# Axis_Channel.net
KiCad netlist of a schematic drawn in Altium Designer
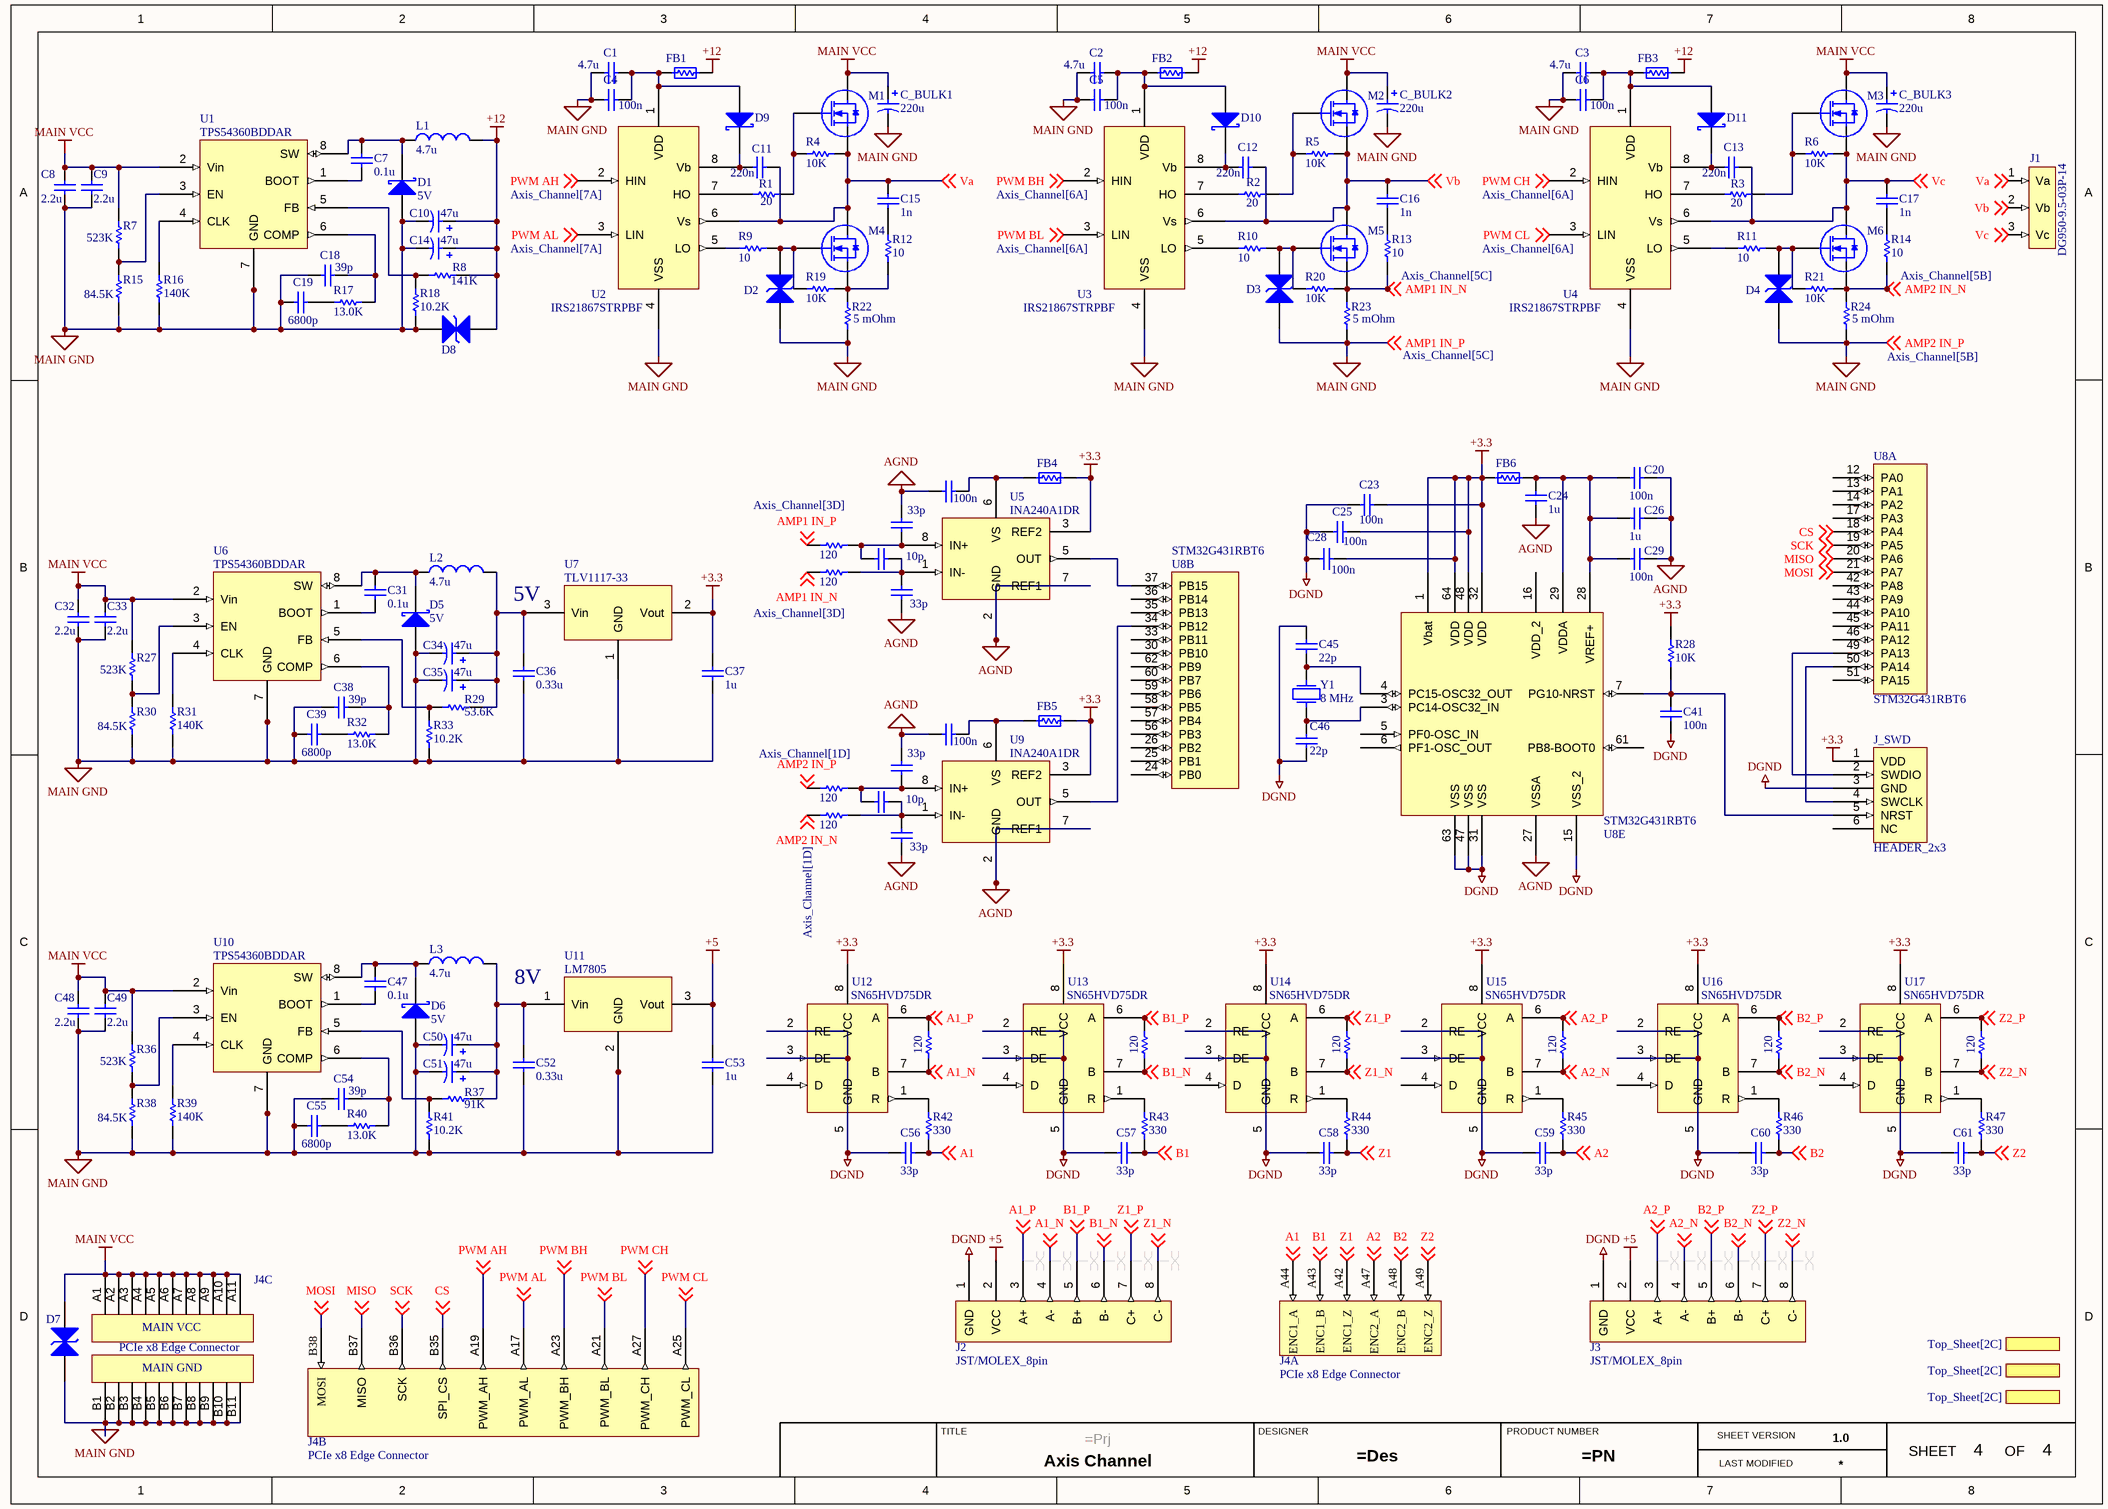
[diagram p0: Axis_Channel.SchDoc]

(export (version "E")
  (design (tool "Eeschema 10.0.6"))
  (components
    (comp (ref "C1")
      (value "4.7u")
      (footprint "1206")
      (description "2.2u-10u")
      (fields (field (name "Comment") "Capacitor 1206"))
      (libsource (lib "Power_Components") (part "Capacitor 1206"))
    )
    (comp (ref "C2")
      (value "4.7u")
      (footprint "1206")
      (description "2.2u-10u")
      (fields (field (name "Comment") "Capacitor 1206"))
      (libsource (lib "Power_Components") (part "Capacitor 1206"))
    )
    (comp (ref "C3")
      (value "4.7u")
      (footprint "1206")
      (description "2.2u-10u")
      (fields (field (name "Comment") "Capacitor 1206"))
      (libsource (lib "Power_Components") (part "Capacitor 1206"))
    )
    (comp (ref "C4")
      (value "100n")
      (footprint "0805")
      (description "0.1u-1u")
      (fields (field (name "Comment") "Capacitor 0805"))
      (libsource (lib "Power_Components") (part "Capacitor 0805"))
    )
    (comp (ref "C5")
      (value "100n")
      (footprint "0805")
      (description "0.1u-1u")
      (fields (field (name "Comment") "Capacitor 0805"))
      (libsource (lib "Power_Components") (part "Capacitor 0805"))
    )
    (comp (ref "C6")
      (value "100n")
      (footprint "0805")
      (description "0.1u-1u")
      (fields (field (name "Comment") "Capacitor 0805"))
      (libsource (lib "Power_Components") (part "Capacitor 0805"))
    )
    (comp (ref "C7")
      (value "0.1u")
      (footprint "0805")
      (description "0.1u-1u")
      (fields (field (name "Comment") "Alum SMD Cap"))
      (libsource (lib "Power_Components") (part "Capacitor 0805"))
    )
    (comp (ref "C8")
      (value "2.2u")
      (footprint "1206")
      (description "2.2u-10u")
      (fields (field (name "Comment") "Alum SMD Cap"))
      (libsource (lib "Power_Components") (part "Capacitor 1206"))
    )
    (comp (ref "C9")
      (value "2.2u")
      (footprint "1206")
      (description "2.2u-10u")
      (fields (field (name "Comment") "Capacitor 1206"))
      (libsource (lib "Power_Components") (part "Capacitor 1206"))
    )
    (comp (ref "C10")
      (value "47u")
      (footprint "ECAP D6.3xL7.7mm")
      (fields (field (name "Comment") "Alum SMD Cap"))
      (libsource (lib "Power_Components") (part "RVT1H470M0607 47UF 50V"))
    )
    (comp (ref "C11")
      (value "220n")
      (footprint "0805")
      (description "0.1u-1u")
      (fields (field (name "Comment") "Capacitor 0805"))
      (libsource (lib "Power_Components") (part "Capacitor 0805"))
    )
    (comp (ref "C12")
      (value "220n")
      (footprint "0805")
      (description "0.1u-1u")
      (fields (field (name "Comment") "Capacitor 0805"))
      (libsource (lib "Power_Components") (part "Capacitor 0805"))
    )
    (comp (ref "C13")
      (value "220n")
      (footprint "0805")
      (description "0.1u-1u")
      (fields (field (name "Comment") "Capacitor 0805"))
      (libsource (lib "Power_Components") (part "Capacitor 0805"))
    )
    (comp (ref "C14")
      (value "47u")
      (footprint "ECAP D6.3xL7.7mm")
      (fields (field (name "Comment") "Alum SMD Cap"))
      (libsource (lib "Power_Components") (part "RVT1H470M0607 47UF 50V"))
    )
    (comp (ref "C15")
      (value "1n")
      (footprint "0805")
      (description "0.1u-1u")
      (fields (field (name "Comment") "Capacitor 0805"))
      (libsource (lib "Power_Components") (part "Capacitor 0805"))
    )
    (comp (ref "C16")
      (value "1n")
      (footprint "0805")
      (description "0.1u-1u")
      (fields (field (name "Comment") "Capacitor 0805"))
      (libsource (lib "Power_Components") (part "Capacitor 0805"))
    )
    (comp (ref "C17")
      (value "1n")
      (footprint "0805")
      (description "0.1u-1u")
      (fields (field (name "Comment") "Capacitor 0805"))
      (libsource (lib "Power_Components") (part "Capacitor 0805"))
    )
    (comp (ref "C18")
      (value "39p")
      (footprint "0805")
      (description "0.1u-1u")
      (fields (field (name "Comment") "Capacitor"))
      (libsource (lib "Power_Components") (part "Capacitor 0805"))
    )
    (comp (ref "C19")
      (value "6800p")
      (footprint "0805")
      (description "0.1u-1u")
      (fields (field (name "Comment") "Capacitor 0805"))
      (libsource (lib "Power_Components") (part "Capacitor 0805"))
    )
    (comp (ref "C20")
      (value "100n")
      (footprint "0805")
      (description "0.1u-1u")
      (fields (field (name "Comment") "Capacitor 0805"))
      (libsource (lib "Power_Components") (part "Capacitor 0805"))
    )
    (comp (ref "C21")
      (value "Cap")
      (footprint "0805")
      (fields (field (name "PARAMETER 1") "100n"))
      (libsource (lib "") (part "Capacitor 0805_1"))
    )
    (comp (ref "C22")
      (value "Cap")
      (footprint "0805")
      (fields (field (name "PARAMETER 1") "33p"))
      (libsource (lib "") (part "Capacitor 0805_1"))
    )
    (comp (ref "C23")
      (value "100n")
      (footprint "0805")
      (description "0.1u-1u")
      (fields (field (name "Comment") "Capacitor 0805"))
      (libsource (lib "Power_Components") (part "Capacitor 0805"))
    )
    (comp (ref "C24")
      (value "1u")
      (footprint "0805")
      (description "0.1u-1u")
      (fields (field (name "Comment") "Capacitor 0805"))
      (libsource (lib "Power_Components") (part "Capacitor 0805"))
    )
    (comp (ref "C25")
      (value "100n")
      (footprint "0805")
      (description "0.1u-1u")
      (fields (field (name "Comment") "Capacitor 0805"))
      (libsource (lib "Power_Components") (part "Capacitor 0805"))
    )
    (comp (ref "C26")
      (value "1u")
      (footprint "0805")
      (description "0.1u-1u")
      (fields (field (name "Comment") "Capacitor 0805"))
      (libsource (lib "Power_Components") (part "Capacitor 0805"))
    )
    (comp (ref "C27")
      (value "Cap")
      (footprint "0805")
      (fields (field (name "PARAMETER 1") "10p"))
      (libsource (lib "") (part "Capacitor 0805_1"))
    )
    (comp (ref "C28")
      (value "100n")
      (footprint "0805")
      (description "0.1u-1u")
      (fields (field (name "Comment") "Capacitor 0805"))
      (libsource (lib "Power_Components") (part "Capacitor 0805"))
    )
    (comp (ref "C29")
      (value "100n")
      (footprint "0805")
      (description "0.1u-1u")
      (fields (field (name "Comment") "Capacitor 0805"))
      (libsource (lib "Power_Components") (part "Capacitor 0805"))
    )
    (comp (ref "C30")
      (value "Cap")
      (footprint "0805")
      (fields (field (name "PARAMETER 1") "33p"))
      (libsource (lib "") (part "Capacitor 0805_1"))
    )
    (comp (ref "C31")
      (value "0.1u")
      (footprint "0805")
      (description "0.1u-1u")
      (fields (field (name "Comment") "Alum SMD Cap"))
      (libsource (lib "Power_Components") (part "Capacitor 0805"))
    )
    (comp (ref "C32")
      (value "2.2u")
      (footprint "1206")
      (description "2.2u-10u")
      (fields (field (name "Comment") "Alum SMD Cap"))
      (libsource (lib "Power_Components") (part "Capacitor 1206"))
    )
    (comp (ref "C33")
      (value "2.2u")
      (footprint "1206")
      (description "2.2u-10u")
      (fields (field (name "Comment") "Capacitor 1206"))
      (libsource (lib "Power_Components") (part "Capacitor 1206"))
    )
    (comp (ref "C34")
      (value "47u")
      (footprint "ECAP D6.3xL7.7mm")
      (fields (field (name "Comment") "Alum SMD Cap"))
      (libsource (lib "Power_Components") (part "RVT1H470M0607 47UF 50V"))
    )
    (comp (ref "C35")
      (value "47u")
      (footprint "ECAP D6.3xL7.7mm")
      (fields (field (name "Comment") "Alum SMD Cap"))
      (libsource (lib "Power_Components") (part "RVT1H470M0607 47UF 50V"))
    )
    (comp (ref "C36")
      (value "0.33u")
      (footprint "0805")
      (description "0.1u-1u")
      (fields (field (name "Comment") "Capacitor 0805"))
      (libsource (lib "Power_Components") (part "Capacitor 0805"))
    )
    (comp (ref "C37")
      (value "1u")
      (footprint "0805")
      (description "0.1u-1u")
      (fields (field (name "Comment") "Capacitor 0805"))
      (libsource (lib "Power_Components") (part "Capacitor 0805"))
    )
    (comp (ref "C38")
      (value "39p")
      (footprint "0805")
      (description "0.1u-1u")
      (fields (field (name "Comment") "Alum SMD Cap"))
      (libsource (lib "Power_Components") (part "Capacitor 0805"))
    )
    (comp (ref "C39")
      (value "6800p")
      (footprint "0805")
      (description "0.1u-1u")
      (fields (field (name "Comment") "Capacitor 0805"))
      (libsource (lib "Power_Components") (part "Capacitor 0805"))
    )
    (comp (ref "C40")
      (value "Cap")
      (footprint "0805")
      (fields (field (name "PARAMETER 1") "100n"))
      (libsource (lib "") (part "Capacitor 0805_1"))
    )
    (comp (ref "C41")
      (value "100n")
      (footprint "0805")
      (description "0.1u-1u")
      (fields (field (name "Comment") "Capacitor 0805"))
      (libsource (lib "Power_Components") (part "Capacitor 0805"))
    )
    (comp (ref "C42")
      (value "33p")
      (footprint "0805")
      (fields (field (name "Comment") "Cap"))
      (libsource (lib "") (part "Capacitor 0805_1"))
    )
    (comp (ref "C43")
      (value "Cap")
      (footprint "0805")
      (fields (field (name "PARAMETER 1") "10p"))
      (libsource (lib "") (part "Capacitor 0805_1"))
    )
    (comp (ref "C44")
      (value "Cap")
      (footprint "0805")
      (fields (field (name "PARAMETER 1") "33p"))
      (libsource (lib "") (part "Capacitor 0805_1"))
    )
    (comp (ref "C45")
      (value "22p")
      (footprint "0805")
      (description "0.1u-1u")
      (fields (field (name "Comment") "Capacitor 0805"))
      (libsource (lib "Power_Components") (part "Capacitor 0805"))
    )
    (comp (ref "C46")
      (value "22p")
      (footprint "0805")
      (description "0.1u-1u")
      (fields (field (name "Comment") "Capacitor 0805"))
      (libsource (lib "Power_Components") (part "Capacitor 0805"))
    )
    (comp (ref "C47")
      (value "0.1u")
      (footprint "0805")
      (description "0.1u-1u")
      (fields (field (name "Comment") "Alum SMD Cap"))
      (libsource (lib "Power_Components") (part "Capacitor 0805"))
    )
    (comp (ref "C48")
      (value "2.2u")
      (footprint "1206")
      (description "2.2u-10u")
      (fields (field (name "Comment") "Alum SMD Cap"))
      (libsource (lib "Power_Components") (part "Capacitor 1206"))
    )
    (comp (ref "C49")
      (value "2.2u")
      (footprint "1206")
      (description "2.2u-10u")
      (fields (field (name "Comment") "Capacitor 1206"))
      (libsource (lib "Power_Components") (part "Capacitor 1206"))
    )
    (comp (ref "C50")
      (value "47u")
      (footprint "ECAP D6.3xL7.7mm")
      (fields (field (name "Comment") "Alum SMD Cap"))
      (libsource (lib "Power_Components") (part "RVT1H470M0607 47UF 50V"))
    )
    (comp (ref "C51")
      (value "47u")
      (footprint "ECAP D6.3xL7.7mm")
      (fields (field (name "Comment") "Alum SMD Cap"))
      (libsource (lib "Power_Components") (part "RVT1H470M0607 47UF 50V"))
    )
    (comp (ref "C52")
      (value "0.33u")
      (footprint "0805")
      (description "0.1u-1u")
      (fields (field (name "Comment") "Capacitor 0805"))
      (libsource (lib "Power_Components") (part "Capacitor 0805"))
    )
    (comp (ref "C53")
      (value "1u")
      (footprint "0805")
      (description "0.1u-1u")
      (fields (field (name "Comment") "Capacitor 0805"))
      (libsource (lib "Power_Components") (part "Capacitor 0805"))
    )
    (comp (ref "C54")
      (value "39p")
      (footprint "0805")
      (description "0.1u-1u")
      (fields (field (name "Comment") "Alum SMD Cap"))
      (libsource (lib "Power_Components") (part "Capacitor 0805"))
    )
    (comp (ref "C55")
      (value "6800p")
      (footprint "0805")
      (description "0.1u-1u")
      (fields (field (name "Comment") "Capacitor 0805"))
      (libsource (lib "Power_Components") (part "Capacitor 0805"))
    )
    (comp (ref "C56")
      (value "33p")
      (footprint "0805")
      (description "0.1u-1u")
      (fields (field (name "Comment") "Capacitor 0805"))
      (libsource (lib "Power_Components") (part "Capacitor 0805"))
    )
    (comp (ref "C57")
      (value "33p")
      (footprint "0805")
      (description "0.1u-1u")
      (fields (field (name "Comment") "Capacitor 0805"))
      (libsource (lib "Power_Components") (part "Capacitor 0805"))
    )
    (comp (ref "C58")
      (value "33p")
      (footprint "0805")
      (description "0.1u-1u")
      (fields (field (name "Comment") "Capacitor 0805"))
      (libsource (lib "Power_Components") (part "Capacitor 0805"))
    )
    (comp (ref "C59")
      (value "33p")
      (footprint "0805")
      (description "0.1u-1u")
      (fields (field (name "Comment") "Capacitor 0805"))
      (libsource (lib "Power_Components") (part "Capacitor 0805"))
    )
    (comp (ref "C60")
      (value "33p")
      (footprint "0805")
      (description "0.1u-1u")
      (fields (field (name "Comment") "Capacitor 0805"))
      (libsource (lib "Power_Components") (part "Capacitor 0805"))
    )
    (comp (ref "C61")
      (value "33p")
      (footprint "0805")
      (description "0.1u-1u")
      (fields (field (name "Comment") "Capacitor 0805"))
      (libsource (lib "Power_Components") (part "Capacitor 0805"))
    )
    (comp (ref "C_BULK1")
      (value "220u")
      (footprint "ECAP 12.5x16.5")
      (description "100V 12.5mm 16.5mm 220uF ±20% SMD,D12.5xL16.5mm Aluminum Electrolytic Capacitors - SMD ROHS")
      (fields (field (name "Comment") "Alum SMD Cap"))
      (libsource (lib "Power_Components") (part "220uF 100V 12.5mm 16.5mm"))
    )
    (comp (ref "C_BULK2")
      (value "220u")
      (footprint "ECAP 12.5x16.5")
      (description "100V 12.5mm 16.5mm 220uF ±20% SMD,D12.5xL16.5mm Aluminum Electrolytic Capacitors - SMD ROHS")
      (fields (field (name "Comment") "Alum SMD Cap"))
      (libsource (lib "Power_Components") (part "220uF 100V 12.5mm 16.5mm"))
    )
    (comp (ref "C_BULK3")
      (value "220u")
      (footprint "ECAP 12.5x16.5")
      (description "100V 12.5mm 16.5mm 220uF ±20% SMD,D12.5xL16.5mm Aluminum Electrolytic Capacitors - SMD ROHS")
      (fields (field (name "Comment") "Alum SMD Cap"))
      (libsource (lib "Power_Components") (part "220uF 100V 12.5mm 16.5mm"))
    )
    (comp (ref "D1")
      (value "5V")
      (footprint "SMB")
      (fields (field (name "Comment") "Schottky Diod"))
      (libsource (lib "Power_Components") (part "Schottky Diod"))
    )
    (comp (ref "D2")
      (value "Supressor Dual")
      (footprint "SMB")
      (description "Suppressor Dual")
      (libsource (lib "Power_Components") (part "Suppressor Dual"))
    )
    (comp (ref "D3")
      (value "Supressor Dual")
      (footprint "SMB")
      (description "Suppressor Dual")
      (libsource (lib "Power_Components") (part "Suppressor Dual"))
    )
    (comp (ref "D4")
      (value "Supressor Dual")
      (footprint "SMB")
      (description "Suppressor Dual")
      (libsource (lib "Power_Components") (part "Suppressor Dual"))
    )
    (comp (ref "D5")
      (value "5V")
      (footprint "SMB")
      (fields (field (name "Comment") "Schottky Diod"))
      (libsource (lib "Power_Components") (part "Schottky Diod"))
    )
    (comp (ref "D6")
      (value "5V")
      (footprint "SMB")
      (fields (field (name "Comment") "Schottky Diod"))
      (libsource (lib "Power_Components") (part "Schottky Diod"))
    )
    (comp (ref "D7")
      (value "Supressor Dual")
      (footprint "SMB")
      (description "Suppressor Dual")
      (libsource (lib "Power_Components") (part "Suppressor Dual"))
    )
    (comp (ref "D8")
      (value "Supressor Dual")
      (footprint "SMB")
      (description "Suppressor Dual")
      (libsource (lib "Power_Components") (part "Suppressor Dual"))
    )
    (comp (ref "D9")
      (value "Schottky Diod")
      (footprint "SMB")
      (libsource (lib "Power_Components") (part "Schottky Diod"))
    )
    (comp (ref "D10")
      (value "Schottky Diod")
      (footprint "SMB")
      (libsource (lib "Power_Components") (part "Schottky Diod"))
    )
    (comp (ref "D11")
      (value "Schottky Diod")
      (footprint "SMB")
      (libsource (lib "Power_Components") (part "Schottky Diod"))
    )
    (comp (ref "FB1")
      (value "Ferrite Bead")
      (footprint "0805")
      (description "600 ohm 100Mhz")
      (libsource (lib "Power_Components") (part "Ferrite Bead"))
    )
    (comp (ref "FB2")
      (value "Ferrite Bead")
      (footprint "0805")
      (description "600 ohm 100Mhz")
      (libsource (lib "Power_Components") (part "Ferrite Bead"))
    )
    (comp (ref "FB3")
      (value "Ferrite Bead")
      (footprint "0805")
      (description "600 ohm 100Mhz")
      (libsource (lib "Power_Components") (part "Ferrite Bead"))
    )
    (comp (ref "FB4")
      (value "Ferrite Bead")
      (footprint "0805")
      (description "600 ohm 100Mhz")
      (libsource (lib "Power_Components") (part "Ferrite Bead"))
    )
    (comp (ref "FB5")
      (value "Ferrite Bead")
      (footprint "0805")
      (description "600 ohm 100Mhz")
      (libsource (lib "Power_Components") (part "Ferrite Bead"))
    )
    (comp (ref "FB6")
      (value "Ferrite Bead")
      (footprint "0805")
      (description "600 ohm 100Mhz")
      (libsource (lib "Power_Components") (part "Ferrite Bead"))
    )
    (comp (ref "J1")
      (value "DG950-9.5-03P-14")
      (footprint "DG950-9.5-03P-14")
      (description "3 pin power")
      (libsource (lib "Power_Components") (part "DG950-9.5-03P-14"))
    )
    (comp (ref "J2")
      (value "JST/MOLEX_8pin")
      (footprint "B8B-EH-A-(LF)(SN)")
      (description "8 pin JST")
      (libsource (lib "Power_Components") (part "JST/MOLEX_8pin"))
    )
    (comp (ref "J3")
      (value "JST/MOLEX_8pin")
      (footprint "B8B-EH-A-(LF)(SN)")
      (description "8 pin JST")
      (libsource (lib "Power_Components") (part "JST/MOLEX_8pin"))
    )
    (comp (ref "J4")
      (value "PCIe x8 Edge Connector")
      (footprint "MALE_PCI_x8")
      (libsource (lib "") (part "CONN_EDGE_PCIe_x8_98P_2"))
    )
    (comp (ref "J_SWD")
      (value "HEADER_2x3")
      (footprint "HEADER_2x3")
      (libsource (lib "Power_Components") (part "HEADER_2x3"))
    )
    (comp (ref "L1")
      (value "4.7u")
      (footprint "MWSA0603S-4R7MT")
      (fields (field (name "Comment") "Inductor"))
      (libsource (lib "Power_Components") (part "Inductor"))
    )
    (comp (ref "L2")
      (value "4.7u")
      (footprint "MWSA0603S-4R7MT")
      (fields (field (name "Comment") "Inductor"))
      (libsource (lib "Power_Components") (part "Inductor"))
    )
    (comp (ref "L3")
      (value "4.7u")
      (footprint "MWSA0603S-4R7MT")
      (fields (field (name "Comment") "Inductor"))
      (libsource (lib "Power_Components") (part "Inductor"))
    )
    (comp (ref "M1")
      (value "NTMFS3D5N08XT1G")
      (footprint "SuperSO8")
      (libsource (lib "Power_Components") (part "BSC030N08NS5"))
    )
    (comp (ref "M2")
      (value "NTMFS3D5N08XT1G")
      (footprint "SuperSO8")
      (libsource (lib "Power_Components") (part "BSC030N08NS5"))
    )
    (comp (ref "M3")
      (value "NTMFS3D5N08XT1G")
      (footprint "SuperSO8")
      (libsource (lib "Power_Components") (part "BSC030N08NS5"))
    )
    (comp (ref "M4")
      (value "NTMFS3D5N08XT1G")
      (footprint "SuperSO8")
      (libsource (lib "Power_Components") (part "BSC030N08NS5"))
    )
    (comp (ref "M5")
      (value "NTMFS3D5N08XT1G")
      (footprint "SuperSO8")
      (libsource (lib "Power_Components") (part "BSC030N08NS5"))
    )
    (comp (ref "M6")
      (value "NTMFS3D5N08XT1G")
      (footprint "SuperSO8")
      (libsource (lib "Power_Components") (part "BSC030N08NS5"))
    )
    (comp (ref "R1")
      (value "20")
      (footprint "0805")
      (fields (field (name "Comment") "Resistor 0805"))
      (libsource (lib "Power_Components") (part "Resistor 0805"))
    )
    (comp (ref "R2")
      (value "20")
      (footprint "0805")
      (fields (field (name "Comment") "Resistor 0805"))
      (libsource (lib "Power_Components") (part "Resistor 0805"))
    )
    (comp (ref "R3")
      (value "20")
      (footprint "0805")
      (fields (field (name "Comment") "Resistor 0805"))
      (libsource (lib "Power_Components") (part "Resistor 0805"))
    )
    (comp (ref "R4")
      (value "10K")
      (footprint "0805")
      (fields (field (name "Comment") "Resistor 0805"))
      (libsource (lib "Power_Components") (part "Resistor 0805"))
    )
    (comp (ref "R5")
      (value "10K")
      (footprint "0805")
      (fields (field (name "Comment") "Resistor 0805"))
      (libsource (lib "Power_Components") (part "Resistor 0805"))
    )
    (comp (ref "R6")
      (value "10K")
      (footprint "0805")
      (fields (field (name "Comment") "Resistor 0805"))
      (libsource (lib "Power_Components") (part "Resistor 0805"))
    )
    (comp (ref "R7")
      (value "523K")
      (footprint "0805")
      (fields (field (name "Comment") "Resistor 0805"))
      (libsource (lib "Power_Components") (part "Resistor 0805"))
    )
    (comp (ref "R8")
      (value "141K")
      (footprint "0805")
      (fields (field (name "Comment") "Resistor 0805"))
      (libsource (lib "Power_Components") (part "Resistor 0805"))
    )
    (comp (ref "R9")
      (value "10")
      (footprint "0805")
      (fields (field (name "Comment") "Resistor 0805"))
      (libsource (lib "Power_Components") (part "Resistor 0805"))
    )
    (comp (ref "R10")
      (value "10")
      (footprint "0805")
      (fields (field (name "Comment") "Resistor 0805"))
      (libsource (lib "Power_Components") (part "Resistor 0805"))
    )
    (comp (ref "R11")
      (value "10")
      (footprint "0805")
      (fields (field (name "Comment") "Resistor 0805"))
      (libsource (lib "Power_Components") (part "Resistor 0805"))
    )
    (comp (ref "R12")
      (value "10")
      (footprint "0805")
      (fields (field (name "Comment") "Resistor 0805"))
      (libsource (lib "Power_Components") (part "Resistor 0805"))
    )
    (comp (ref "R13")
      (value "10")
      (footprint "0805")
      (fields (field (name "Comment") "Resistor 0805"))
      (libsource (lib "Power_Components") (part "Resistor 0805"))
    )
    (comp (ref "R14")
      (value "10")
      (footprint "0805")
      (fields (field (name "Comment") "Resistor 0805"))
      (libsource (lib "Power_Components") (part "Resistor 0805"))
    )
    (comp (ref "R15")
      (value "84.5K")
      (footprint "0805")
      (fields (field (name "Comment") "Resistor 0805"))
      (libsource (lib "Power_Components") (part "Resistor 0805"))
    )
    (comp (ref "R16")
      (value "140K")
      (footprint "0805")
      (fields (field (name "Comment") "Resistor 0805"))
      (libsource (lib "Power_Components") (part "Resistor 0805"))
    )
    (comp (ref "R17")
      (value "13.0K")
      (footprint "0805")
      (fields (field (name "Comment") "Resistor 0805"))
      (libsource (lib "Power_Components") (part "Resistor 0805"))
    )
    (comp (ref "R18")
      (value "10.2K")
      (footprint "0805")
      (fields (field (name "Comment") "Resistor 0805"))
      (libsource (lib "Power_Components") (part "Resistor 0805"))
    )
    (comp (ref "R19")
      (value "10K")
      (footprint "0805")
      (fields (field (name "Comment") "Resistor 0805"))
      (libsource (lib "Power_Components") (part "Resistor 0805"))
    )
    (comp (ref "R20")
      (value "10K")
      (footprint "0805")
      (fields (field (name "Comment") "Resistor 0805"))
      (libsource (lib "Power_Components") (part "Resistor 0805"))
    )
    (comp (ref "R21")
      (value "10K")
      (footprint "0805")
      (fields (field (name "Comment") "Resistor 0805"))
      (libsource (lib "Power_Components") (part "Resistor 0805"))
    )
    (comp (ref "R22")
      (value "5 mOhm")
      (footprint "2512")
      (description "Current Shunt")
      (libsource (lib "Power_Components") (part "Current Shunt"))
    )
    (comp (ref "R23")
      (value "5 mOhm")
      (footprint "2512")
      (description "Current Shunt")
      (libsource (lib "Power_Components") (part "Current Shunt"))
    )
    (comp (ref "R24")
      (value "5 mOhm")
      (footprint "2512")
      (description "Current Shunt")
      (libsource (lib "Power_Components") (part "Current Shunt"))
    )
    (comp (ref "R25")
      (value "120")
      (footprint "0805")
      (fields (field (name "Comment") "Resistor"))
      (libsource (lib "") (part "Resistor 0805_1"))
    )
    (comp (ref "R26")
      (value "120")
      (footprint "0805")
      (fields (field (name "Comment") "Resistor"))
      (libsource (lib "") (part "Resistor 0805_1"))
    )
    (comp (ref "R27")
      (value "523K")
      (footprint "0805")
      (fields (field (name "Comment") "Resistor 0805"))
      (libsource (lib "Power_Components") (part "Resistor 0805"))
    )
    (comp (ref "R28")
      (value "10K")
      (footprint "0805")
      (fields (field (name "Comment") "Resistor 0805"))
      (libsource (lib "Power_Components") (part "Resistor 0805"))
    )
    (comp (ref "R29")
      (value "53.6K")
      (footprint "0805")
      (fields (field (name "Comment") "Resistor 0805"))
      (libsource (lib "Power_Components") (part "Resistor 0805"))
    )
    (comp (ref "R30")
      (value "84.5K")
      (footprint "0805")
      (fields (field (name "Comment") "Resistor 0805"))
      (libsource (lib "Power_Components") (part "Resistor 0805"))
    )
    (comp (ref "R31")
      (value "140K")
      (footprint "0805")
      (fields (field (name "Comment") "Resistor 0805"))
      (libsource (lib "Power_Components") (part "Resistor 0805"))
    )
    (comp (ref "R32")
      (value "13.0K")
      (footprint "0805")
      (fields (field (name "Comment") "Resistor 0805"))
      (libsource (lib "Power_Components") (part "Resistor 0805"))
    )
    (comp (ref "R33")
      (value "10.2K")
      (footprint "0805")
      (fields (field (name "Comment") "Resistor 0805"))
      (libsource (lib "Power_Components") (part "Resistor 0805"))
    )
    (comp (ref "R34")
      (value "120")
      (footprint "0805")
      (fields (field (name "Comment") "Resistor"))
      (libsource (lib "") (part "Resistor 0805_1"))
    )
    (comp (ref "R35")
      (value "120")
      (footprint "0805")
      (fields (field (name "Comment") "Resistor"))
      (libsource (lib "") (part "Resistor 0805_1"))
    )
    (comp (ref "R36")
      (value "523K")
      (footprint "0805")
      (fields (field (name "Comment") "Resistor 0805"))
      (libsource (lib "Power_Components") (part "Resistor 0805"))
    )
    (comp (ref "R37")
      (value "91K")
      (footprint "0805")
      (fields (field (name "Comment") "Resistor 0805"))
      (libsource (lib "Power_Components") (part "Resistor 0805"))
    )
    (comp (ref "R38")
      (value "84.5K")
      (footprint "0805")
      (fields (field (name "Comment") "Resistor 0805"))
      (libsource (lib "Power_Components") (part "Resistor 0805"))
    )
    (comp (ref "R39")
      (value "140K")
      (footprint "0805")
      (fields (field (name "Comment") "Resistor 0805"))
      (libsource (lib "Power_Components") (part "Resistor 0805"))
    )
    (comp (ref "R40")
      (value "13.0K")
      (footprint "0805")
      (fields (field (name "Comment") "Resistor 0805"))
      (libsource (lib "Power_Components") (part "Resistor 0805"))
    )
    (comp (ref "R41")
      (value "10.2K")
      (footprint "0805")
      (fields (field (name "Comment") "Resistor 0805"))
      (libsource (lib "Power_Components") (part "Resistor 0805"))
    )
    (comp (ref "R42")
      (value "330")
      (footprint "0805")
      (fields (field (name "Comment") "Resistor 0805"))
      (libsource (lib "Power_Components") (part "Resistor 0805"))
    )
    (comp (ref "R43")
      (value "330")
      (footprint "0805")
      (fields (field (name "Comment") "Resistor 0805"))
      (libsource (lib "Power_Components") (part "Resistor 0805"))
    )
    (comp (ref "R44")
      (value "330")
      (footprint "0805")
      (fields (field (name "Comment") "Resistor 0805"))
      (libsource (lib "Power_Components") (part "Resistor 0805"))
    )
    (comp (ref "R45")
      (value "330")
      (footprint "0805")
      (fields (field (name "Comment") "Resistor 0805"))
      (libsource (lib "Power_Components") (part "Resistor 0805"))
    )
    (comp (ref "R46")
      (value "330")
      (footprint "0805")
      (fields (field (name "Comment") "Resistor 0805"))
      (libsource (lib "Power_Components") (part "Resistor 0805"))
    )
    (comp (ref "R47")
      (value "330")
      (footprint "0805")
      (fields (field (name "Comment") "Resistor 0805"))
      (libsource (lib "Power_Components") (part "Resistor 0805"))
    )
    (comp (ref "R48")
      (value "120")
      (footprint "0805")
      (fields (field (name "Comment") "Resistor"))
      (libsource (lib "Power_Components") (part "Resistor 0805"))
    )
    (comp (ref "R49")
      (value "120")
      (footprint "0805")
      (fields (field (name "Comment") "Resistor"))
      (libsource (lib "Power_Components") (part "Resistor 0805"))
    )
    (comp (ref "R50")
      (value "120")
      (footprint "0805")
      (fields (field (name "Comment") "Resistor"))
      (libsource (lib "Power_Components") (part "Resistor 0805"))
    )
    (comp (ref "R51")
      (value "120")
      (footprint "0805")
      (fields (field (name "Comment") "Resistor"))
      (libsource (lib "Power_Components") (part "Resistor 0805"))
    )
    (comp (ref "R52")
      (value "120")
      (footprint "0805")
      (fields (field (name "Comment") "Resistor"))
      (libsource (lib "Power_Components") (part "Resistor 0805"))
    )
    (comp (ref "R53")
      (value "120")
      (footprint "0805")
      (fields (field (name "Comment") "Resistor"))
      (libsource (lib "Power_Components") (part "Resistor 0805"))
    )
    (comp (ref "U1")
      (value "TPS54360BDDAR")
      (footprint "HSOIC-8-DDA")
      (description "Step down DC/DC")
      (libsource (lib "Power_Components") (part "TPS54360BDDAR"))
    )
    (comp (ref "U2")
      (value "IRS21867STRPBF")
      (footprint "SOIC-8")
      (libsource (lib "Power_Components") (part "IRS21867STRPBF"))
    )
    (comp (ref "U3")
      (value "IRS21867STRPBF")
      (footprint "SOIC-8")
      (libsource (lib "Power_Components") (part "IRS21867STRPBF"))
    )
    (comp (ref "U4")
      (value "IRS21867STRPBF")
      (footprint "SOIC-8")
      (libsource (lib "Power_Components") (part "IRS21867STRPBF"))
    )
    (comp (ref "U5")
      (value "INA240A1DR")
      (footprint "SOIC-8")
      (description "Amplifier. A1=20 V/V and +-6.75 Mohm for shunt")
      (libsource (lib "Power_Components") (part "INA240A1DR"))
    )
    (comp (ref "U6")
      (value "TPS54360BDDAR")
      (footprint "HSOIC-8-DDA")
      (description "Step down DC/DC")
      (libsource (lib "Power_Components") (part "TPS54360BDDAR"))
    )
    (comp (ref "U7")
      (value "TLV1117-33")
      (footprint "SOT-223")
      (description "LDO 3.3V")
      (libsource (lib "Power_Components") (part "TLV1117-33IDCYR"))
    )
    (comp (ref "U8")
      (value "STM32G431RBT6")
      (footprint "LQFP-64_10x10_P0.5")
      (description "STM32 with ADC")
      (libsource (lib "Power_Components") (part "STM32G431RBT6"))
    )
    (comp (ref "U9")
      (value "INA240A1DR")
      (footprint "SOIC-8")
      (description "Amplifier. A1=20 V/V and +-6.75 Mohm for shunt")
      (libsource (lib "Power_Components") (part "INA240A1DR"))
    )
    (comp (ref "U10")
      (value "TPS54360BDDAR")
      (footprint "HSOIC-8-DDA")
      (description "Step down DC/DC")
      (libsource (lib "Power_Components") (part "TPS54360BDDAR"))
    )
    (comp (ref "U11")
      (value "LM7805")
      (footprint "TO-263-3")
      (description "Output Current up to 1A")
      (libsource (lib "Power_Components") (part "LM7805"))
    )
    (comp (ref "U12")
      (value "SN65HVD75DR")
      (footprint "SOIC-8")
      (description "20 Mbps RS-422/485")
      (libsource (lib "Power_Components") (part "SN65HVD75DR"))
    )
    (comp (ref "U13")
      (value "SN65HVD75DR")
      (footprint "SOIC-8")
      (description "20 Mbps RS-422/485")
      (libsource (lib "Power_Components") (part "SN65HVD75DR"))
    )
    (comp (ref "U14")
      (value "SN65HVD75DR")
      (footprint "SOIC-8")
      (description "20 Mbps RS-422/485")
      (libsource (lib "Power_Components") (part "SN65HVD75DR"))
    )
    (comp (ref "U15")
      (value "SN65HVD75DR")
      (footprint "SOIC-8")
      (description "20 Mbps RS-422/485")
      (libsource (lib "Power_Components") (part "SN65HVD75DR"))
    )
    (comp (ref "U16")
      (value "SN65HVD75DR")
      (footprint "SOIC-8")
      (description "20 Mbps RS-422/485")
      (libsource (lib "Power_Components") (part "SN65HVD75DR"))
    )
    (comp (ref "U17")
      (value "SN65HVD75DR")
      (footprint "SOIC-8")
      (description "20 Mbps RS-422/485")
      (libsource (lib "Power_Components") (part "SN65HVD75DR"))
    )
    (comp (ref "Y1")
      (value "8 MHz")
      (footprint "hc-49sm")
      (fields (field (name "Comment") "OSC"))
      (libsource (lib "Power_Components") (part "Crystal"))
    )
  )
  (nets
    (net (code "2") (name "+3.3") (class "Default")
      (node (ref "C23") (pin "2") (pinfunction "2_2") (pintype "passive"))
      (node (ref "C25") (pin "2") (pinfunction "2_2") (pintype "passive"))
      (node (ref "C28") (pin "2") (pinfunction "2_2") (pintype "passive"))
      (node (ref "C37") (pin "2") (pinfunction "2_2") (pintype "passive"))
      (node (ref "FB4") (pin "2") (pinfunction "2_2") (pintype "passive"))
      (node (ref "FB5") (pin "2") (pinfunction "2_2") (pintype "passive"))
      (node (ref "FB6") (pin "1") (pinfunction "1_1") (pintype "passive"))
      (node (ref "J_SWD") (pin "1") (pinfunction "VDD_1") (pintype "passive"))
      (node (ref "R28") (pin "2") (pinfunction "2_2") (pintype "passive"))
      (node (ref "U12") (pin "8") (pinfunction "VCC_8") (pintype "passive"))
      (node (ref "U13") (pin "8") (pinfunction "VCC_8") (pintype "passive"))
      (node (ref "U14") (pin "8") (pinfunction "VCC_8") (pintype "passive"))
      (node (ref "U15") (pin "8") (pinfunction "VCC_8") (pintype "passive"))
      (node (ref "U16") (pin "8") (pinfunction "VCC_8") (pintype "passive"))
      (node (ref "U17") (pin "8") (pinfunction "VCC_8") (pintype "passive"))
      (node (ref "U5") (pin "3") (pinfunction "REF2_3") (pintype "passive"))
      (node (ref "U7") (pin "2") (pinfunction "Vout_2") (pintype "passive"))
      (node (ref "U7") (pin "4") (pinfunction "Vout_4") (pintype "passive"))
      (node (ref "U8") (pin "1") (pinfunction "Vbat_1") (pintype "passive"))
      (node (ref "U8") (pin "32") (pinfunction "VDD_32") (pintype "passive"))
      (node (ref "U8") (pin "48") (pinfunction "VDD_48") (pintype "passive"))
      (node (ref "U8") (pin "64") (pinfunction "VDD_64") (pintype "passive"))
      (node (ref "U9") (pin "3") (pinfunction "REF2_3") (pintype "passive"))
    )
    (net (code "3") (name "+5") (class "Default")
      (node (ref "C53") (pin "2") (pinfunction "2_2") (pintype "passive"))
      (node (ref "J2") (pin "2") (pinfunction "VCC_2") (pintype "passive"))
      (node (ref "J3") (pin "2") (pinfunction "VCC_2") (pintype "passive"))
      (node (ref "U11") (pin "3") (pinfunction "Vout_3") (pintype "passive"))
    )
    (net (code "4") (name "+12") (class "Default")
      (node (ref "C10") (pin "1") (pinfunction "1_1") (pintype "passive"))
      (node (ref "C14") (pin "1") (pinfunction "1_1") (pintype "passive"))
      (node (ref "D8") (pin "2") (pinfunction "2_2") (pintype "passive"))
      (node (ref "FB1") (pin "2") (pinfunction "2_2") (pintype "passive"))
      (node (ref "FB2") (pin "2") (pinfunction "2_2") (pintype "passive"))
      (node (ref "FB3") (pin "2") (pinfunction "2_2") (pintype "passive"))
      (node (ref "L1") (pin "2") (pinfunction "2_2") (pintype "passive"))
      (node (ref "R8") (pin "1") (pinfunction "1_1") (pintype "passive"))
    )
    (net (code "7") (name "A1") (class "Default")
      (node (ref "C56") (pin "2") (pinfunction "2_2") (pintype "passive"))
      (node (ref "J4") (pin "A44") (pinfunction "ENC1_A_A44") (pintype "input"))
      (node (ref "R42") (pin "2") (pinfunction "2_2") (pintype "passive"))
    )
    (net (code "8") (name "A1_N") (class "Default")
      (node (ref "J2") (pin "4") (pinfunction "A-_4") (pintype "output"))
      (node (ref "R48") (pin "2") (pinfunction "2_2") (pintype "passive"))
      (node (ref "U12") (pin "7") (pinfunction "B_7") (pintype "passive"))
    )
    (net (code "9") (name "A1_P") (class "Default")
      (node (ref "J2") (pin "3") (pinfunction "A+_3") (pintype "output"))
      (node (ref "R48") (pin "1") (pinfunction "1_1") (pintype "passive"))
      (node (ref "U12") (pin "6") (pinfunction "A_6") (pintype "passive"))
    )
    (net (code "10") (name "A2") (class "Default")
      (node (ref "C59") (pin "2") (pinfunction "2_2") (pintype "passive"))
      (node (ref "J4") (pin "A47") (pinfunction "ENC2_A_A47") (pintype "input"))
      (node (ref "R45") (pin "2") (pinfunction "2_2") (pintype "passive"))
    )
    (net (code "11") (name "A2_N") (class "Default")
      (node (ref "J3") (pin "4") (pinfunction "A-_4") (pintype "output"))
      (node (ref "R51") (pin "2") (pinfunction "2_2") (pintype "passive"))
      (node (ref "U15") (pin "7") (pinfunction "B_7") (pintype "passive"))
    )
    (net (code "12") (name "A2_P") (class "Default")
      (node (ref "J3") (pin "3") (pinfunction "A+_3") (pintype "output"))
      (node (ref "R51") (pin "1") (pinfunction "1_1") (pintype "passive"))
      (node (ref "U15") (pin "6") (pinfunction "A_6") (pintype "passive"))
    )
    (net (code "13") (name "AGND") (class "Default")
      (node (ref "C20") (pin "2") (pinfunction "2_2") (pintype "passive"))
      (node (ref "C21") (pin "2") (pinfunction "2_2") (pintype "passive"))
      (node (ref "C22") (pin "2") (pinfunction "2_2") (pintype "passive"))
      (node (ref "C24") (pin "1") (pinfunction "1_1") (pintype "passive"))
      (node (ref "C26") (pin "2") (pinfunction "2_2") (pintype "passive"))
      (node (ref "C29") (pin "2") (pinfunction "2_2") (pintype "passive"))
      (node (ref "C30") (pin "1") (pinfunction "1_1") (pintype "passive"))
      (node (ref "C40") (pin "2") (pinfunction "2_2") (pintype "passive"))
      (node (ref "C42") (pin "2") (pinfunction "2_2") (pintype "passive"))
      (node (ref "C44") (pin "1") (pinfunction "1_1") (pintype "passive"))
      (node (ref "U5") (pin "2") (pinfunction "GND_2") (pintype "passive"))
      (node (ref "U5") (pin "7") (pinfunction "REF1_7") (pintype "passive"))
      (node (ref "U8") (pin "27") (pinfunction "VSSA_27") (pintype "passive"))
      (node (ref "U9") (pin "2") (pinfunction "GND_2") (pintype "passive"))
      (node (ref "U9") (pin "7") (pinfunction "REF1_7") (pintype "passive"))
    )
    (net (code "14") (name "AMP1 IN_N") (class "Default")
      (node (ref "M5") (pin "1") (pinfunction "S_1") (pintype "passive"))
      (node (ref "M5") (pin "2") (pinfunction "S_2") (pintype "passive"))
      (node (ref "M5") (pin "3") (pinfunction "S_3") (pintype "passive"))
      (node (ref "R13") (pin "1") (pinfunction "1_1") (pintype "passive"))
      (node (ref "R20") (pin "1") (pinfunction "1_1") (pintype "passive"))
      (node (ref "R23") (pin "2") (pinfunction "2_2") (pintype "passive"))
      (node (ref "R26") (pin "1") (pinfunction "1_1") (pintype "passive"))
    )
    (net (code "15") (name "AMP1 IN_P") (class "Default")
      (node (ref "C1") (pin "2") (pinfunction "2_2") (pintype "passive"))
      (node (ref "C10") (pin "2") (pinfunction "2_2") (pintype "passive"))
      (node (ref "C14") (pin "2") (pinfunction "2_2") (pintype "passive"))
      (node (ref "C18") (pin "2") (pinfunction "2_2") (pintype "passive"))
      (node (ref "C19") (pin "2") (pinfunction "2_2") (pintype "passive"))
      (node (ref "C2") (pin "2") (pinfunction "2_2") (pintype "passive"))
      (node (ref "C3") (pin "2") (pinfunction "2_2") (pintype "passive"))
      (node (ref "C32") (pin "1") (pinfunction "1_1") (pintype "passive"))
      (node (ref "C33") (pin "1") (pinfunction "1_1") (pintype "passive"))
      (node (ref "C34") (pin "2") (pinfunction "2_2") (pintype "passive"))
      (node (ref "C35") (pin "2") (pinfunction "2_2") (pintype "passive"))
      (node (ref "C36") (pin "1") (pinfunction "1_1") (pintype "passive"))
      (node (ref "C37") (pin "1") (pinfunction "1_1") (pintype "passive"))
      (node (ref "C38") (pin "2") (pinfunction "2_2") (pintype "passive"))
      (node (ref "C39") (pin "2") (pinfunction "2_2") (pintype "passive"))
      (node (ref "C4") (pin "2") (pinfunction "2_2") (pintype "passive"))
      (node (ref "C48") (pin "1") (pinfunction "1_1") (pintype "passive"))
      (node (ref "C49") (pin "1") (pinfunction "1_1") (pintype "passive"))
      (node (ref "C5") (pin "2") (pinfunction "2_2") (pintype "passive"))
      (node (ref "C50") (pin "2") (pinfunction "2_2") (pintype "passive"))
      (node (ref "C51") (pin "2") (pinfunction "2_2") (pintype "passive"))
      (node (ref "C52") (pin "1") (pinfunction "1_1") (pintype "passive"))
      (node (ref "C53") (pin "1") (pinfunction "1_1") (pintype "passive"))
      (node (ref "C54") (pin "2") (pinfunction "2_2") (pintype "passive"))
      (node (ref "C55") (pin "2") (pinfunction "2_2") (pintype "passive"))
      (node (ref "C6") (pin "2") (pinfunction "2_2") (pintype "passive"))
      (node (ref "C8") (pin "1") (pinfunction "1_1") (pintype "passive"))
      (node (ref "C9") (pin "1") (pinfunction "1_1") (pintype "passive"))
      (node (ref "C_BULK1") (pin "2") (pinfunction "2_2") (pintype "passive"))
      (node (ref "C_BULK2") (pin "2") (pinfunction "2_2") (pintype "passive"))
      (node (ref "C_BULK3") (pin "2") (pinfunction "2_2") (pintype "passive"))
      (node (ref "D1") (pin "1") (pinfunction "A_1") (pintype "passive"))
      (node (ref "D2") (pin "1") (pinfunction "1_1") (pintype "passive"))
      (node (ref "D3") (pin "1") (pinfunction "1_1") (pintype "passive"))
      (node (ref "D4") (pin "1") (pinfunction "1_1") (pintype "passive"))
      (node (ref "D5") (pin "1") (pinfunction "A_1") (pintype "passive"))
      (node (ref "D6") (pin "1") (pinfunction "A_1") (pintype "passive"))
      (node (ref "D7") (pin "1") (pinfunction "1_1") (pintype "passive"))
      (node (ref "D8") (pin "1") (pinfunction "1_1") (pintype "passive"))
      (node (ref "J4") (pin "B1") (pinfunction "A19_B1") (pintype "power_in"))
      (node (ref "J4") (pin "B10") (pinfunction "A28_B10") (pintype "power_in"))
      (node (ref "J4") (pin "B11") (pinfunction "A29_B11") (pintype "power_in"))
      (node (ref "J4") (pin "B2") (pinfunction "A20_B2") (pintype "power_in"))
      (node (ref "J4") (pin "B3") (pinfunction "A21_B3") (pintype "power_in"))
      (node (ref "J4") (pin "B4") (pinfunction "A22_B4") (pintype "power_in"))
      (node (ref "J4") (pin "B5") (pinfunction "A23_B5") (pintype "power_in"))
      (node (ref "J4") (pin "B6") (pinfunction "A24_B6") (pintype "power_in"))
      (node (ref "J4") (pin "B7") (pinfunction "A25_B7") (pintype "power_in"))
      (node (ref "J4") (pin "B8") (pinfunction "A26_B8") (pintype "power_in"))
      (node (ref "J4") (pin "B9") (pinfunction "A27_B9") (pintype "power_in"))
      (node (ref "R15") (pin "1") (pinfunction "1_1") (pintype "passive"))
      (node (ref "R16") (pin "1") (pinfunction "1_1") (pintype "passive"))
      (node (ref "R18") (pin "1") (pinfunction "1_1") (pintype "passive"))
      (node (ref "R22") (pin "1") (pinfunction "1_1") (pintype "passive"))
      (node (ref "R23") (pin "1") (pinfunction "1_1") (pintype "passive"))
      (node (ref "R24") (pin "1") (pinfunction "1_1") (pintype "passive"))
      (node (ref "R25") (pin "1") (pinfunction "1_1") (pintype "passive"))
      (node (ref "R30") (pin "1") (pinfunction "1_1") (pintype "passive"))
      (node (ref "R31") (pin "1") (pinfunction "1_1") (pintype "passive"))
      (node (ref "R33") (pin "1") (pinfunction "1_1") (pintype "passive"))
      (node (ref "R34") (pin "1") (pinfunction "1_1") (pintype "passive"))
      (node (ref "R38") (pin "1") (pinfunction "1_1") (pintype "passive"))
      (node (ref "R39") (pin "1") (pinfunction "1_1") (pintype "passive"))
      (node (ref "R41") (pin "1") (pinfunction "1_1") (pintype "passive"))
      (node (ref "U1") (pin "7") (pinfunction "GND_7") (pintype "passive"))
      (node (ref "U1") (pin "9") (pinfunction "GND_9") (pintype "passive"))
      (node (ref "U10") (pin "7") (pinfunction "GND_7") (pintype "passive"))
      (node (ref "U10") (pin "9") (pinfunction "GND_9") (pintype "passive"))
      (node (ref "U11") (pin "2") (pinfunction "GND_2") (pintype "passive"))
      (node (ref "U11") (pin "4") (pinfunction "GND_4") (pintype "passive"))
      (node (ref "U2") (pin "4") (pinfunction "VSS_4") (pintype "passive"))
      (node (ref "U3") (pin "4") (pinfunction "VSS_4") (pintype "passive"))
      (node (ref "U4") (pin "4") (pinfunction "VSS_4") (pintype "passive"))
      (node (ref "U6") (pin "7") (pinfunction "GND_7") (pintype "passive"))
      (node (ref "U6") (pin "9") (pinfunction "GND_9") (pintype "passive"))
      (node (ref "U7") (pin "1") (pinfunction "GND_1") (pintype "passive"))
    )
    (net (code "16") (name "AMP2 IN_N") (class "Default")
      (node (ref "M6") (pin "1") (pinfunction "S_1") (pintype "passive"))
      (node (ref "M6") (pin "2") (pinfunction "S_2") (pintype "passive"))
      (node (ref "M6") (pin "3") (pinfunction "S_3") (pintype "passive"))
      (node (ref "R14") (pin "1") (pinfunction "1_1") (pintype "passive"))
      (node (ref "R21") (pin "1") (pinfunction "1_1") (pintype "passive"))
      (node (ref "R24") (pin "2") (pinfunction "2_2") (pintype "passive"))
      (node (ref "R35") (pin "1") (pinfunction "1_1") (pintype "passive"))
    )
    (net (code "17") (name "B1") (class "Default")
      (node (ref "C57") (pin "2") (pinfunction "2_2") (pintype "passive"))
      (node (ref "J4") (pin "A43") (pinfunction "ENC1_B_A43") (pintype "input"))
      (node (ref "R43") (pin "2") (pinfunction "2_2") (pintype "passive"))
    )
    (net (code "18") (name "B1_N") (class "Default")
      (node (ref "J2") (pin "6") (pinfunction "B-_6") (pintype "output"))
      (node (ref "R49") (pin "2") (pinfunction "2_2") (pintype "passive"))
      (node (ref "U13") (pin "7") (pinfunction "B_7") (pintype "passive"))
    )
    (net (code "19") (name "B1_P") (class "Default")
      (node (ref "J2") (pin "5") (pinfunction "B+_5") (pintype "output"))
      (node (ref "R49") (pin "1") (pinfunction "1_1") (pintype "passive"))
      (node (ref "U13") (pin "6") (pinfunction "A_6") (pintype "passive"))
    )
    (net (code "20") (name "B2") (class "Default")
      (node (ref "C60") (pin "2") (pinfunction "2_2") (pintype "passive"))
      (node (ref "J4") (pin "A48") (pinfunction "ENC2_B_A48") (pintype "input"))
      (node (ref "R46") (pin "2") (pinfunction "2_2") (pintype "passive"))
    )
    (net (code "21") (name "B2_N") (class "Default")
      (node (ref "J3") (pin "6") (pinfunction "B-_6") (pintype "output"))
      (node (ref "R52") (pin "2") (pinfunction "2_2") (pintype "passive"))
      (node (ref "U16") (pin "7") (pinfunction "B_7") (pintype "passive"))
    )
    (net (code "22") (name "B2_P") (class "Default")
      (node (ref "J3") (pin "5") (pinfunction "B+_5") (pintype "output"))
      (node (ref "R52") (pin "1") (pinfunction "1_1") (pintype "passive"))
      (node (ref "U16") (pin "6") (pinfunction "A_6") (pintype "passive"))
    )
    (net (code "23") (name "CS") (class "Default")
      (node (ref "J4") (pin "B35") (pinfunction "SPI_CS_B35") (pintype "output"))
      (node (ref "U8") (pin "18") (pinfunction "PA4_18") (pintype "bidirectional"))
    )
    (net (code "24") (name "DGND") (class "Default")
      (node (ref "C23") (pin "1") (pinfunction "1_1") (pintype "passive"))
      (node (ref "C25") (pin "1") (pinfunction "1_1") (pintype "passive"))
      (node (ref "C28") (pin "1") (pinfunction "1_1") (pintype "passive"))
      (node (ref "C41") (pin "1") (pinfunction "1_1") (pintype "passive"))
      (node (ref "C45") (pin "1") (pinfunction "1_1") (pintype "passive"))
      (node (ref "C46") (pin "1") (pinfunction "1_1") (pintype "passive"))
      (node (ref "C56") (pin "1") (pinfunction "1_1") (pintype "passive"))
      (node (ref "C57") (pin "1") (pinfunction "1_1") (pintype "passive"))
      (node (ref "C58") (pin "1") (pinfunction "1_1") (pintype "passive"))
      (node (ref "C59") (pin "1") (pinfunction "1_1") (pintype "passive"))
      (node (ref "C60") (pin "1") (pinfunction "1_1") (pintype "passive"))
      (node (ref "C61") (pin "1") (pinfunction "1_1") (pintype "passive"))
      (node (ref "J2") (pin "1") (pinfunction "GND_1") (pintype "passive"))
      (node (ref "J3") (pin "1") (pinfunction "GND_1") (pintype "passive"))
      (node (ref "J_SWD") (pin "3") (pinfunction "GND_3") (pintype "passive"))
      (node (ref "U12") (pin "2") (pinfunction "RE_2") (pintype "passive"))
      (node (ref "U12") (pin "3") (pinfunction "DE_3") (pintype "input"))
      (node (ref "U12") (pin "5") (pinfunction "GND_5") (pintype "passive"))
      (node (ref "U13") (pin "2") (pinfunction "RE_2") (pintype "passive"))
      (node (ref "U13") (pin "3") (pinfunction "DE_3") (pintype "input"))
      (node (ref "U13") (pin "5") (pinfunction "GND_5") (pintype "passive"))
      (node (ref "U14") (pin "2") (pinfunction "RE_2") (pintype "passive"))
      (node (ref "U14") (pin "3") (pinfunction "DE_3") (pintype "input"))
      (node (ref "U14") (pin "5") (pinfunction "GND_5") (pintype "passive"))
      (node (ref "U15") (pin "2") (pinfunction "RE_2") (pintype "passive"))
      (node (ref "U15") (pin "3") (pinfunction "DE_3") (pintype "input"))
      (node (ref "U15") (pin "5") (pinfunction "GND_5") (pintype "passive"))
      (node (ref "U16") (pin "2") (pinfunction "RE_2") (pintype "passive"))
      (node (ref "U16") (pin "3") (pinfunction "DE_3") (pintype "input"))
      (node (ref "U16") (pin "5") (pinfunction "GND_5") (pintype "passive"))
      (node (ref "U17") (pin "2") (pinfunction "RE_2") (pintype "passive"))
      (node (ref "U17") (pin "3") (pinfunction "DE_3") (pintype "input"))
      (node (ref "U17") (pin "5") (pinfunction "GND_5") (pintype "passive"))
      (node (ref "U8") (pin "15") (pinfunction "VSS_2_15") (pintype "passive"))
      (node (ref "U8") (pin "31") (pinfunction "VSS_31") (pintype "passive"))
      (node (ref "U8") (pin "47") (pinfunction "VSS_47") (pintype "passive"))
      (node (ref "U8") (pin "63") (pinfunction "VSS_63") (pintype "passive"))
    )
    (net (code "25") (name "MAIN VCC") (class "Default")
      (node (ref "C32") (pin "2") (pinfunction "2_2") (pintype "passive"))
      (node (ref "C33") (pin "2") (pinfunction "2_2") (pintype "passive"))
      (node (ref "C48") (pin "2") (pinfunction "2_2") (pintype "passive"))
      (node (ref "C49") (pin "2") (pinfunction "2_2") (pintype "passive"))
      (node (ref "C8") (pin "2") (pinfunction "2_2") (pintype "passive"))
      (node (ref "C9") (pin "2") (pinfunction "2_2") (pintype "passive"))
      (node (ref "C_BULK1") (pin "1") (pinfunction "1_1") (pintype "passive"))
      (node (ref "C_BULK2") (pin "1") (pinfunction "1_1") (pintype "passive"))
      (node (ref "C_BULK3") (pin "1") (pinfunction "1_1") (pintype "passive"))
      (node (ref "D7") (pin "2") (pinfunction "2_2") (pintype "passive"))
      (node (ref "J4") (pin "A1") (pintype "power_in"))
      (node (ref "J4") (pin "A10") (pintype "power_in"))
      (node (ref "J4") (pin "A11") (pintype "power_in"))
      (node (ref "J4") (pin "A2") (pintype "power_in"))
      (node (ref "J4") (pin "A3") (pintype "power_in"))
      (node (ref "J4") (pin "A4") (pintype "power_in"))
      (node (ref "J4") (pin "A5") (pintype "power_in"))
      (node (ref "J4") (pin "A6") (pintype "power_in"))
      (node (ref "J4") (pin "A7") (pintype "power_in"))
      (node (ref "J4") (pin "A8") (pintype "power_in"))
      (node (ref "J4") (pin "A9") (pintype "power_in"))
      (node (ref "M1") (pin "5") (pinfunction "D_5") (pintype "passive"))
      (node (ref "M1") (pin "6") (pinfunction "D_6") (pintype "passive"))
      (node (ref "M1") (pin "7") (pinfunction "D_7") (pintype "passive"))
      (node (ref "M1") (pin "8") (pinfunction "D_8") (pintype "passive"))
      (node (ref "M2") (pin "5") (pinfunction "D_5") (pintype "passive"))
      (node (ref "M2") (pin "6") (pinfunction "D_6") (pintype "passive"))
      (node (ref "M2") (pin "7") (pinfunction "D_7") (pintype "passive"))
      (node (ref "M2") (pin "8") (pinfunction "D_8") (pintype "passive"))
      (node (ref "M3") (pin "5") (pinfunction "D_5") (pintype "passive"))
      (node (ref "M3") (pin "6") (pinfunction "D_6") (pintype "passive"))
      (node (ref "M3") (pin "7") (pinfunction "D_7") (pintype "passive"))
      (node (ref "M3") (pin "8") (pinfunction "D_8") (pintype "passive"))
      (node (ref "R27") (pin "2") (pinfunction "2_2") (pintype "passive"))
      (node (ref "R36") (pin "2") (pinfunction "2_2") (pintype "passive"))
      (node (ref "R7") (pin "2") (pinfunction "2_2") (pintype "passive"))
      (node (ref "U1") (pin "2") (pinfunction "Vin_2") (pintype "input"))
      (node (ref "U10") (pin "2") (pinfunction "Vin_2") (pintype "input"))
      (node (ref "U6") (pin "2") (pinfunction "Vin_2") (pintype "input"))
    )
    (net (code "26") (name "MISO") (class "Default")
      (node (ref "J4") (pin "B37") (pinfunction "MISO_B37") (pintype "output"))
      (node (ref "U8") (pin "20") (pinfunction "PA6_20") (pintype "bidirectional"))
    )
    (net (code "27") (name "MOSI") (class "Default")
      (node (ref "J4") (pin "B38") (pinfunction "MOSI_B38") (pintype "input"))
      (node (ref "U8") (pin "21") (pinfunction "PA7_21") (pintype "bidirectional"))
    )
    (net (code "28") (name "Net-(C15-Pad2)") (class "Default")
      (node (ref "C15") (pin "2") (pinfunction "2_2") (pintype "passive"))
      (node (ref "R12") (pin "2") (pinfunction "2_2") (pintype "passive"))
    )
    (net (code "29") (name "Net-(C16-Pad2)") (class "Default")
      (node (ref "C16") (pin "2") (pinfunction "2_2") (pintype "passive"))
      (node (ref "R13") (pin "2") (pinfunction "2_2") (pintype "passive"))
    )
    (net (code "30") (name "Net-(C17-Pad2)") (class "Default")
      (node (ref "C17") (pin "2") (pinfunction "2_2") (pintype "passive"))
      (node (ref "R14") (pin "2") (pinfunction "2_2") (pintype "passive"))
    )
    (net (code "31") (name "Net-(C19-Pad1)") (class "Default")
      (node (ref "C19") (pin "1") (pinfunction "1_1") (pintype "passive"))
      (node (ref "R17") (pin "2") (pinfunction "2_2") (pintype "passive"))
    )
    (net (code "32") (name "Net-(C39-Pad1)") (class "Default")
      (node (ref "C39") (pin "1") (pinfunction "1_1") (pintype "passive"))
      (node (ref "R32") (pin "2") (pinfunction "2_2") (pintype "passive"))
    )
    (net (code "33") (name "Net-(C55-Pad1)") (class "Default")
      (node (ref "C55") (pin "1") (pinfunction "1_1") (pintype "passive"))
      (node (ref "R40") (pin "2") (pinfunction "2_2") (pintype "passive"))
    )
    (net (code "34") (name "Net-(D1-K)") (class "Default")
      (node (ref "C7") (pin "1") (pinfunction "1_1") (pintype "passive"))
      (node (ref "D1") (pin "2") (pinfunction "K_2") (pintype "passive"))
      (node (ref "L1") (pin "1") (pinfunction "1_1") (pintype "passive"))
      (node (ref "U1") (pin "8") (pinfunction "SW_8") (pintype "bidirectional"))
    )
    (net (code "35") (name "Net-(D5-K)") (class "Default")
      (node (ref "C31") (pin "1") (pinfunction "1_1") (pintype "passive"))
      (node (ref "D5") (pin "2") (pinfunction "K_2") (pintype "passive"))
      (node (ref "L2") (pin "1") (pinfunction "1_1") (pintype "passive"))
      (node (ref "U6") (pin "8") (pinfunction "SW_8") (pintype "bidirectional"))
    )
    (net (code "36") (name "Net-(D6-K)") (class "Default")
      (node (ref "C47") (pin "1") (pinfunction "1_1") (pintype "passive"))
      (node (ref "D6") (pin "2") (pinfunction "K_2") (pintype "passive"))
      (node (ref "L3") (pin "1") (pinfunction "1_1") (pintype "passive"))
      (node (ref "U10") (pin "8") (pinfunction "SW_8") (pintype "bidirectional"))
    )
    (net (code "37") (name "Net-(D9-A)") (class "Default")
      (node (ref "C1") (pin "1") (pinfunction "1_1") (pintype "passive"))
      (node (ref "C4") (pin "1") (pinfunction "1_1") (pintype "passive"))
      (node (ref "D9") (pin "1") (pinfunction "A_1") (pintype "passive"))
      (node (ref "FB1") (pin "1") (pinfunction "1_1") (pintype "passive"))
      (node (ref "U2") (pin "1") (pinfunction "VDD_1") (pintype "power_in"))
    )
    (net (code "38") (name "Net-(D9-K)") (class "Default")
      (node (ref "C11") (pin "2") (pinfunction "2_2") (pintype "passive"))
      (node (ref "D9") (pin "2") (pinfunction "K_2") (pintype "passive"))
      (node (ref "U2") (pin "8") (pinfunction "Vb_8") (pintype "passive"))
    )
    (net (code "39") (name "Net-(D10-A)") (class "Default")
      (node (ref "C2") (pin "1") (pinfunction "1_1") (pintype "passive"))
      (node (ref "C5") (pin "1") (pinfunction "1_1") (pintype "passive"))
      (node (ref "D10") (pin "1") (pinfunction "A_1") (pintype "passive"))
      (node (ref "FB2") (pin "1") (pinfunction "1_1") (pintype "passive"))
      (node (ref "U3") (pin "1") (pinfunction "VDD_1") (pintype "power_in"))
    )
    (net (code "40") (name "Net-(D10-K)") (class "Default")
      (node (ref "C12") (pin "2") (pinfunction "2_2") (pintype "passive"))
      (node (ref "D10") (pin "2") (pinfunction "K_2") (pintype "passive"))
      (node (ref "U3") (pin "8") (pinfunction "Vb_8") (pintype "passive"))
    )
    (net (code "41") (name "Net-(D11-A)") (class "Default")
      (node (ref "C3") (pin "1") (pinfunction "1_1") (pintype "passive"))
      (node (ref "C6") (pin "1") (pinfunction "1_1") (pintype "passive"))
      (node (ref "D11") (pin "1") (pinfunction "A_1") (pintype "passive"))
      (node (ref "FB3") (pin "1") (pinfunction "1_1") (pintype "passive"))
      (node (ref "U4") (pin "1") (pinfunction "VDD_1") (pintype "power_in"))
    )
    (net (code "42") (name "Net-(D11-K)") (class "Default")
      (node (ref "C13") (pin "2") (pinfunction "2_2") (pintype "passive"))
      (node (ref "D11") (pin "2") (pinfunction "K_2") (pintype "passive"))
      (node (ref "U4") (pin "8") (pinfunction "Vb_8") (pintype "passive"))
    )
    (net (code "43") (name "Net-(J_SWD-NRST)") (class "Default")
      (node (ref "C41") (pin "2") (pinfunction "2_2") (pintype "passive"))
      (node (ref "J_SWD") (pin "5") (pinfunction "NRST_5") (pintype "input"))
      (node (ref "R28") (pin "1") (pinfunction "1_1") (pintype "passive"))
      (node (ref "U8") (pin "7") (pinfunction "PG10-NRST_7") (pintype "bidirectional"))
    )
    (net (code "44") (name "Net-(J_SWD-SWCLK)") (class "Default")
      (node (ref "J_SWD") (pin "4") (pinfunction "SWCLK_4") (pintype "input"))
      (node (ref "U8") (pin "50") (pinfunction "PA14_50") (pintype "bidirectional"))
    )
    (net (code "45") (name "Net-(J_SWD-SWDIO)") (class "Default")
      (node (ref "J_SWD") (pin "2") (pinfunction "SWDIO_2") (pintype "input"))
      (node (ref "U8") (pin "49") (pinfunction "PA13_49") (pintype "bidirectional"))
    )
    (net (code "46") (name "Net-(M1-G)") (class "Default")
      (node (ref "M1") (pin "4") (pinfunction "G_4") (pintype "passive"))
      (node (ref "R1") (pin "1") (pinfunction "1_1") (pintype "passive"))
      (node (ref "R4") (pin "2") (pinfunction "2_2") (pintype "passive"))
    )
    (net (code "47") (name "Net-(M2-G)") (class "Default")
      (node (ref "M2") (pin "4") (pinfunction "G_4") (pintype "passive"))
      (node (ref "R2") (pin "1") (pinfunction "1_1") (pintype "passive"))
      (node (ref "R5") (pin "2") (pinfunction "2_2") (pintype "passive"))
    )
    (net (code "48") (name "Net-(M3-G)") (class "Default")
      (node (ref "M3") (pin "4") (pinfunction "G_4") (pintype "passive"))
      (node (ref "R3") (pin "2") (pinfunction "2_2") (pintype "passive"))
      (node (ref "R6") (pin "2") (pinfunction "2_2") (pintype "passive"))
    )
    (net (code "49") (name "Net-(M4-G)") (class "Default")
      (node (ref "D2") (pin "2") (pinfunction "2_2") (pintype "passive"))
      (node (ref "M4") (pin "4") (pinfunction "G_4") (pintype "passive"))
      (node (ref "R19") (pin "2") (pinfunction "2_2") (pintype "passive"))
      (node (ref "R9") (pin "2") (pinfunction "2_2") (pintype "passive"))
    )
    (net (code "50") (name "Net-(M4-S-Pad1)") (class "Default")
      (node (ref "M4") (pin "1") (pinfunction "S_1") (pintype "passive"))
      (node (ref "M4") (pin "2") (pinfunction "S_2") (pintype "passive"))
      (node (ref "M4") (pin "3") (pinfunction "S_3") (pintype "passive"))
      (node (ref "R12") (pin "1") (pinfunction "1_1") (pintype "passive"))
      (node (ref "R19") (pin "1") (pinfunction "1_1") (pintype "passive"))
      (node (ref "R22") (pin "2") (pinfunction "2_2") (pintype "passive"))
    )
    (net (code "51") (name "Net-(M5-G)") (class "Default")
      (node (ref "D3") (pin "2") (pinfunction "2_2") (pintype "passive"))
      (node (ref "M5") (pin "4") (pinfunction "G_4") (pintype "passive"))
      (node (ref "R10") (pin "2") (pinfunction "2_2") (pintype "passive"))
      (node (ref "R20") (pin "2") (pinfunction "2_2") (pintype "passive"))
    )
    (net (code "52") (name "Net-(M6-G)") (class "Default")
      (node (ref "D4") (pin "2") (pinfunction "2_2") (pintype "passive"))
      (node (ref "M6") (pin "4") (pinfunction "G_4") (pintype "passive"))
      (node (ref "R11") (pin "2") (pinfunction "2_2") (pintype "passive"))
      (node (ref "R21") (pin "2") (pinfunction "2_2") (pintype "passive"))
    )
    (net (code "53") (name "Net-(U1-BOOT)") (class "Default")
      (node (ref "C7") (pin "2") (pinfunction "2_2") (pintype "passive"))
      (node (ref "U1") (pin "1") (pinfunction "BOOT_1") (pintype "output"))
    )
    (net (code "54") (name "Net-(U1-CLK)") (class "Default")
      (node (ref "R16") (pin "2") (pinfunction "2_2") (pintype "passive"))
      (node (ref "U1") (pin "4") (pinfunction "CLK_4") (pintype "input"))
    )
    (net (code "55") (name "Net-(U1-COMP)") (class "Default")
      (node (ref "C18") (pin "1") (pinfunction "1_1") (pintype "passive"))
      (node (ref "R17") (pin "1") (pinfunction "1_1") (pintype "passive"))
      (node (ref "U1") (pin "6") (pinfunction "COMP_6") (pintype "output"))
    )
    (net (code "56") (name "Net-(U1-EN)") (class "Default")
      (node (ref "R15") (pin "2") (pinfunction "2_2") (pintype "passive"))
      (node (ref "R7") (pin "1") (pinfunction "1_1") (pintype "passive"))
      (node (ref "U1") (pin "3") (pinfunction "EN_3") (pintype "input"))
    )
    (net (code "57") (name "Net-(U1-FB)") (class "Default")
      (node (ref "R18") (pin "2") (pinfunction "2_2") (pintype "passive"))
      (node (ref "R8") (pin "2") (pinfunction "2_2") (pintype "passive"))
      (node (ref "U1") (pin "5") (pinfunction "FB_5") (pintype "input"))
    )
    (net (code "58") (name "Net-(U2-HO)") (class "Default")
      (node (ref "R1") (pin "2") (pinfunction "2_2") (pintype "passive"))
      (node (ref "U2") (pin "7") (pinfunction "HO_7") (pintype "passive"))
    )
    (net (code "59") (name "Net-(U2-LO)") (class "Default")
      (node (ref "R9") (pin "1") (pinfunction "1_1") (pintype "passive"))
      (node (ref "U2") (pin "5") (pinfunction "LO_5") (pintype "output"))
    )
    (net (code "60") (name "Net-(U3-HO)") (class "Default")
      (node (ref "R2") (pin "2") (pinfunction "2_2") (pintype "passive"))
      (node (ref "U3") (pin "7") (pinfunction "HO_7") (pintype "passive"))
    )
    (net (code "61") (name "Net-(U3-LO)") (class "Default")
      (node (ref "R10") (pin "1") (pinfunction "1_1") (pintype "passive"))
      (node (ref "U3") (pin "5") (pinfunction "LO_5") (pintype "output"))
    )
    (net (code "62") (name "Net-(U4-HO)") (class "Default")
      (node (ref "R3") (pin "1") (pinfunction "1_1") (pintype "passive"))
      (node (ref "U4") (pin "7") (pinfunction "HO_7") (pintype "passive"))
    )
    (net (code "63") (name "Net-(U4-LO)") (class "Default")
      (node (ref "R11") (pin "1") (pinfunction "1_1") (pintype "passive"))
      (node (ref "U4") (pin "5") (pinfunction "LO_5") (pintype "output"))
    )
    (net (code "64") (name "Net-(U5-IN+)") (class "Default")
      (node (ref "C22") (pin "1") (pinfunction "1_1") (pintype "passive"))
      (node (ref "C27") (pin "2") (pinfunction "2_2") (pintype "passive"))
      (node (ref "R25") (pin "2") (pinfunction "2_2") (pintype "passive"))
      (node (ref "U5") (pin "8") (pinfunction "IN+_8") (pintype "input"))
    )
    (net (code "65") (name "Net-(U5-IN-)") (class "Default")
      (node (ref "C27") (pin "1") (pinfunction "1_1") (pintype "passive"))
      (node (ref "C30") (pin "2") (pinfunction "2_2") (pintype "passive"))
      (node (ref "R26") (pin "2") (pinfunction "2_2") (pintype "passive"))
      (node (ref "U5") (pin "1") (pinfunction "IN-_1") (pintype "input"))
    )
    (net (code "66") (name "Net-(U5-OUT)") (class "Default")
      (node (ref "U5") (pin "5") (pinfunction "OUT_5") (pintype "output"))
      (node (ref "U8") (pin "37") (pinfunction "PB15_37") (pintype "bidirectional"))
    )
    (net (code "67") (name "Net-(U5-VS)") (class "Default")
      (node (ref "C21") (pin "1") (pinfunction "1_1") (pintype "passive"))
      (node (ref "FB4") (pin "1") (pinfunction "1_1") (pintype "passive"))
      (node (ref "U5") (pin "6") (pinfunction "VS_6") (pintype "passive"))
    )
    (net (code "68") (name "Net-(U6-BOOT)") (class "Default")
      (node (ref "C31") (pin "2") (pinfunction "2_2") (pintype "passive"))
      (node (ref "U6") (pin "1") (pinfunction "BOOT_1") (pintype "output"))
    )
    (net (code "69") (name "Net-(U6-CLK)") (class "Default")
      (node (ref "R31") (pin "2") (pinfunction "2_2") (pintype "passive"))
      (node (ref "U6") (pin "4") (pinfunction "CLK_4") (pintype "input"))
    )
    (net (code "70") (name "Net-(U6-COMP)") (class "Default")
      (node (ref "C38") (pin "1") (pinfunction "1_1") (pintype "passive"))
      (node (ref "R32") (pin "1") (pinfunction "1_1") (pintype "passive"))
      (node (ref "U6") (pin "6") (pinfunction "COMP_6") (pintype "output"))
    )
    (net (code "71") (name "Net-(U6-EN)") (class "Default")
      (node (ref "R27") (pin "1") (pinfunction "1_1") (pintype "passive"))
      (node (ref "R30") (pin "2") (pinfunction "2_2") (pintype "passive"))
      (node (ref "U6") (pin "3") (pinfunction "EN_3") (pintype "input"))
    )
    (net (code "72") (name "Net-(U6-FB)") (class "Default")
      (node (ref "R29") (pin "2") (pinfunction "2_2") (pintype "passive"))
      (node (ref "R33") (pin "2") (pinfunction "2_2") (pintype "passive"))
      (node (ref "U6") (pin "5") (pinfunction "FB_5") (pintype "input"))
    )
    (net (code "73") (name "Net-(U7-Vin)") (class "Default")
      (node (ref "C34") (pin "1") (pinfunction "1_1") (pintype "passive"))
      (node (ref "C35") (pin "1") (pinfunction "1_1") (pintype "passive"))
      (node (ref "C36") (pin "2") (pinfunction "2_2") (pintype "passive"))
      (node (ref "L2") (pin "2") (pinfunction "2_2") (pintype "passive"))
      (node (ref "R29") (pin "1") (pinfunction "1_1") (pintype "passive"))
      (node (ref "U7") (pin "3") (pinfunction "Vin_3") (pintype "passive"))
    )
    (net (code "74") (name "Net-(U8B-PB12)") (class "Default")
      (node (ref "U8") (pin "34") (pinfunction "PB12_34") (pintype "bidirectional"))
      (node (ref "U9") (pin "5") (pinfunction "OUT_5") (pintype "output"))
    )
    (net (code "75") (name "Net-(U8E-PC14-OSC32_IN)") (class "Default")
      (node (ref "C46") (pin "2") (pinfunction "2_2") (pintype "passive"))
      (node (ref "U8") (pin "3") (pinfunction "PC14-OSC32_IN_3") (pintype "bidirectional"))
      (node (ref "Y1") (pin "2") (pinfunction "2_2") (pintype "passive"))
    )
    (net (code "76") (name "Net-(U8E-PC15-OSC32_OUT)") (class "Default")
      (node (ref "C45") (pin "2") (pinfunction "2_2") (pintype "passive"))
      (node (ref "U8") (pin "4") (pinfunction "PC15-OSC32_OUT_4") (pintype "bidirectional"))
      (node (ref "Y1") (pin "1") (pinfunction "1_1") (pintype "passive"))
    )
    (net (code "77") (name "Net-(U8E-VDDA)") (class "Default")
      (node (ref "C20") (pin "1") (pinfunction "1_1") (pintype "passive"))
      (node (ref "C24") (pin "2") (pinfunction "2_2") (pintype "passive"))
      (node (ref "C26") (pin "1") (pinfunction "1_1") (pintype "passive"))
      (node (ref "C29") (pin "1") (pinfunction "1_1") (pintype "passive"))
      (node (ref "FB6") (pin "2") (pinfunction "2_2") (pintype "passive"))
      (node (ref "U8") (pin "28") (pinfunction "VREF+_28") (pintype "passive"))
      (node (ref "U8") (pin "29") (pinfunction "VDDA_29") (pintype "passive"))
    )
    (net (code "78") (name "Net-(U9-IN+)") (class "Default")
      (node (ref "C42") (pin "1") (pinfunction "1_1") (pintype "passive"))
      (node (ref "C43") (pin "2") (pinfunction "2_2") (pintype "passive"))
      (node (ref "R34") (pin "2") (pinfunction "2_2") (pintype "passive"))
      (node (ref "U9") (pin "8") (pinfunction "IN+_8") (pintype "input"))
    )
    (net (code "79") (name "Net-(U9-IN-)") (class "Default")
      (node (ref "C43") (pin "1") (pinfunction "1_1") (pintype "passive"))
      (node (ref "C44") (pin "2") (pinfunction "2_2") (pintype "passive"))
      (node (ref "R35") (pin "2") (pinfunction "2_2") (pintype "passive"))
      (node (ref "U9") (pin "1") (pinfunction "IN-_1") (pintype "input"))
    )
    (net (code "80") (name "Net-(U9-VS)") (class "Default")
      (node (ref "C40") (pin "1") (pinfunction "1_1") (pintype "passive"))
      (node (ref "FB5") (pin "1") (pinfunction "1_1") (pintype "passive"))
      (node (ref "U9") (pin "6") (pinfunction "VS_6") (pintype "passive"))
    )
    (net (code "81") (name "Net-(U10-BOOT)") (class "Default")
      (node (ref "C47") (pin "2") (pinfunction "2_2") (pintype "passive"))
      (node (ref "U10") (pin "1") (pinfunction "BOOT_1") (pintype "output"))
    )
    (net (code "82") (name "Net-(U10-CLK)") (class "Default")
      (node (ref "R39") (pin "2") (pinfunction "2_2") (pintype "passive"))
      (node (ref "U10") (pin "4") (pinfunction "CLK_4") (pintype "input"))
    )
    (net (code "83") (name "Net-(U10-COMP)") (class "Default")
      (node (ref "C54") (pin "1") (pinfunction "1_1") (pintype "passive"))
      (node (ref "R40") (pin "1") (pinfunction "1_1") (pintype "passive"))
      (node (ref "U10") (pin "6") (pinfunction "COMP_6") (pintype "output"))
    )
    (net (code "84") (name "Net-(U10-EN)") (class "Default")
      (node (ref "R36") (pin "1") (pinfunction "1_1") (pintype "passive"))
      (node (ref "R38") (pin "2") (pinfunction "2_2") (pintype "passive"))
      (node (ref "U10") (pin "3") (pinfunction "EN_3") (pintype "input"))
    )
    (net (code "85") (name "Net-(U10-FB)") (class "Default")
      (node (ref "R37") (pin "2") (pinfunction "2_2") (pintype "passive"))
      (node (ref "R41") (pin "2") (pinfunction "2_2") (pintype "passive"))
      (node (ref "U10") (pin "5") (pinfunction "FB_5") (pintype "input"))
    )
    (net (code "86") (name "Net-(U11-Vin)") (class "Default")
      (node (ref "C50") (pin "1") (pinfunction "1_1") (pintype "passive"))
      (node (ref "C51") (pin "1") (pinfunction "1_1") (pintype "passive"))
      (node (ref "C52") (pin "2") (pinfunction "2_2") (pintype "passive"))
      (node (ref "L3") (pin "2") (pinfunction "2_2") (pintype "passive"))
      (node (ref "R37") (pin "1") (pinfunction "1_1") (pintype "passive"))
      (node (ref "U11") (pin "1") (pinfunction "Vin_1") (pintype "passive"))
    )
    (net (code "87") (name "Net-(U12-R)") (class "Default")
      (node (ref "R42") (pin "1") (pinfunction "1_1") (pintype "passive"))
      (node (ref "U12") (pin "1") (pinfunction "R_1") (pintype "output"))
    )
    (net (code "88") (name "Net-(U13-R)") (class "Default")
      (node (ref "R43") (pin "1") (pinfunction "1_1") (pintype "passive"))
      (node (ref "U13") (pin "1") (pinfunction "R_1") (pintype "output"))
    )
    (net (code "89") (name "Net-(U14-R)") (class "Default")
      (node (ref "R44") (pin "1") (pinfunction "1_1") (pintype "passive"))
      (node (ref "U14") (pin "1") (pinfunction "R_1") (pintype "output"))
    )
    (net (code "90") (name "Net-(U15-R)") (class "Default")
      (node (ref "R45") (pin "1") (pinfunction "1_1") (pintype "passive"))
      (node (ref "U15") (pin "1") (pinfunction "R_1") (pintype "output"))
    )
    (net (code "91") (name "Net-(U16-R)") (class "Default")
      (node (ref "R46") (pin "1") (pinfunction "1_1") (pintype "passive"))
      (node (ref "U16") (pin "1") (pinfunction "R_1") (pintype "output"))
    )
    (net (code "92") (name "Net-(U17-R)") (class "Default")
      (node (ref "R47") (pin "1") (pinfunction "1_1") (pintype "passive"))
      (node (ref "U17") (pin "1") (pinfunction "R_1") (pintype "output"))
    )
    (net (code "93") (name "PWM AH") (class "Default")
      (node (ref "J4") (pin "A19") (pinfunction "PWM_AH_A19") (pintype "output"))
      (node (ref "U2") (pin "2") (pinfunction "HIN_2") (pintype "input"))
    )
    (net (code "94") (name "PWM AL") (class "Default")
      (node (ref "J4") (pin "A17") (pinfunction "PWM_AL_A17") (pintype "output"))
      (node (ref "U2") (pin "3") (pinfunction "LIN_3") (pintype "input"))
    )
    (net (code "95") (name "PWM BH") (class "Default")
      (node (ref "J4") (pin "A23") (pinfunction "PWM_BH_A23") (pintype "output"))
      (node (ref "U3") (pin "2") (pinfunction "HIN_2") (pintype "input"))
    )
    (net (code "96") (name "PWM BL") (class "Default")
      (node (ref "J4") (pin "A21") (pinfunction "PWM_BL_A21") (pintype "output"))
      (node (ref "U3") (pin "3") (pinfunction "LIN_3") (pintype "input"))
    )
    (net (code "97") (name "PWM CH") (class "Default")
      (node (ref "J4") (pin "A27") (pinfunction "PWM_CH_A27") (pintype "output"))
      (node (ref "U4") (pin "2") (pinfunction "HIN_2") (pintype "input"))
    )
    (net (code "98") (name "PWM CL") (class "Default")
      (node (ref "J4") (pin "A25") (pinfunction "PWM_CL_A25") (pintype "output"))
      (node (ref "U4") (pin "3") (pinfunction "LIN_3") (pintype "input"))
    )
    (net (code "99") (name "SCK") (class "Default")
      (node (ref "J4") (pin "B36") (pinfunction "SCK_B36") (pintype "output"))
      (node (ref "U8") (pin "19") (pinfunction "PA5_19") (pintype "bidirectional"))
    )
    (net (code "100") (name "Va") (class "Default")
      (node (ref "C11") (pin "1") (pinfunction "1_1") (pintype "passive"))
      (node (ref "C15") (pin "1") (pinfunction "1_1") (pintype "passive"))
      (node (ref "J1") (pin "1") (pinfunction "Va_1") (pintype "input"))
      (node (ref "M1") (pin "1") (pinfunction "S_1") (pintype "passive"))
      (node (ref "M1") (pin "2") (pinfunction "S_2") (pintype "passive"))
      (node (ref "M1") (pin "3") (pinfunction "S_3") (pintype "passive"))
      (node (ref "M4") (pin "5") (pinfunction "D_5") (pintype "passive"))
      (node (ref "M4") (pin "6") (pinfunction "D_6") (pintype "passive"))
      (node (ref "M4") (pin "7") (pinfunction "D_7") (pintype "passive"))
      (node (ref "M4") (pin "8") (pinfunction "D_8") (pintype "passive"))
      (node (ref "R4") (pin "1") (pinfunction "1_1") (pintype "passive"))
      (node (ref "U2") (pin "6") (pinfunction "Vs_6") (pintype "output"))
    )
    (net (code "101") (name "Vb") (class "Default")
      (node (ref "C12") (pin "1") (pinfunction "1_1") (pintype "passive"))
      (node (ref "C16") (pin "1") (pinfunction "1_1") (pintype "passive"))
      (node (ref "J1") (pin "2") (pinfunction "Vb_2") (pintype "input"))
      (node (ref "M2") (pin "1") (pinfunction "S_1") (pintype "passive"))
      (node (ref "M2") (pin "2") (pinfunction "S_2") (pintype "passive"))
      (node (ref "M2") (pin "3") (pinfunction "S_3") (pintype "passive"))
      (node (ref "M5") (pin "5") (pinfunction "D_5") (pintype "passive"))
      (node (ref "M5") (pin "6") (pinfunction "D_6") (pintype "passive"))
      (node (ref "M5") (pin "7") (pinfunction "D_7") (pintype "passive"))
      (node (ref "M5") (pin "8") (pinfunction "D_8") (pintype "passive"))
      (node (ref "R5") (pin "1") (pinfunction "1_1") (pintype "passive"))
      (node (ref "U3") (pin "6") (pinfunction "Vs_6") (pintype "output"))
    )
    (net (code "102") (name "Vc") (class "Default")
      (node (ref "C13") (pin "1") (pinfunction "1_1") (pintype "passive"))
      (node (ref "C17") (pin "1") (pinfunction "1_1") (pintype "passive"))
      (node (ref "J1") (pin "3") (pinfunction "Vc_3") (pintype "input"))
      (node (ref "M3") (pin "1") (pinfunction "S_1") (pintype "passive"))
      (node (ref "M3") (pin "2") (pinfunction "S_2") (pintype "passive"))
      (node (ref "M3") (pin "3") (pinfunction "S_3") (pintype "passive"))
      (node (ref "M6") (pin "5") (pinfunction "D_5") (pintype "passive"))
      (node (ref "M6") (pin "6") (pinfunction "D_6") (pintype "passive"))
      (node (ref "M6") (pin "7") (pinfunction "D_7") (pintype "passive"))
      (node (ref "M6") (pin "8") (pinfunction "D_8") (pintype "passive"))
      (node (ref "R6") (pin "1") (pinfunction "1_1") (pintype "passive"))
      (node (ref "U4") (pin "6") (pinfunction "Vs_6") (pintype "output"))
    )
    (net (code "103") (name "Z1") (class "Default")
      (node (ref "C58") (pin "2") (pinfunction "2_2") (pintype "passive"))
      (node (ref "J4") (pin "A42") (pinfunction "ENC1_Z_A42") (pintype "input"))
      (node (ref "R44") (pin "2") (pinfunction "2_2") (pintype "passive"))
    )
    (net (code "104") (name "Z1_N") (class "Default")
      (node (ref "J2") (pin "8") (pinfunction "C-_8") (pintype "output"))
      (node (ref "R50") (pin "2") (pinfunction "2_2") (pintype "passive"))
      (node (ref "U14") (pin "7") (pinfunction "B_7") (pintype "passive"))
    )
    (net (code "105") (name "Z1_P") (class "Default")
      (node (ref "J2") (pin "7") (pinfunction "C+_7") (pintype "output"))
      (node (ref "R50") (pin "1") (pinfunction "1_1") (pintype "passive"))
      (node (ref "U14") (pin "6") (pinfunction "A_6") (pintype "passive"))
    )
    (net (code "106") (name "Z2") (class "Default")
      (node (ref "C61") (pin "2") (pinfunction "2_2") (pintype "passive"))
      (node (ref "J4") (pin "A49") (pinfunction "ENC2_Z_A49") (pintype "input"))
      (node (ref "R47") (pin "2") (pinfunction "2_2") (pintype "passive"))
    )
    (net (code "107") (name "Z2_N") (class "Default")
      (node (ref "J3") (pin "8") (pinfunction "C-_8") (pintype "output"))
      (node (ref "R53") (pin "2") (pinfunction "2_2") (pintype "passive"))
      (node (ref "U17") (pin "7") (pinfunction "B_7") (pintype "passive"))
    )
    (net (code "108") (name "Z2_P") (class "Default")
      (node (ref "J3") (pin "7") (pinfunction "C+_7") (pintype "output"))
      (node (ref "R53") (pin "1") (pinfunction "1_1") (pintype "passive"))
      (node (ref "U17") (pin "6") (pinfunction "A_6") (pintype "passive"))
    )
    (net (code "109") (name "unconnected-(J_SWD-NC-Pad6)") (class "Default")
      (node (ref "J_SWD") (pin "6") (pinfunction "NC_6") (pintype "passive"))
    )
    (net (code "110") (name "unconnected-(U8A-PA0-Pad12)") (class "Default")
      (node (ref "U8") (pin "12") (pinfunction "PA0_12") (pintype "bidirectional"))
    )
    (net (code "111") (name "unconnected-(U8A-PA1-Pad13)") (class "Default")
      (node (ref "U8") (pin "13") (pinfunction "PA1_13") (pintype "bidirectional"))
    )
    (net (code "112") (name "unconnected-(U8A-PA2-Pad14)") (class "Default")
      (node (ref "U8") (pin "14") (pinfunction "PA2_14") (pintype "bidirectional"))
    )
    (net (code "113") (name "unconnected-(U8A-PA3-Pad17)") (class "Default")
      (node (ref "U8") (pin "17") (pinfunction "PA3_17") (pintype "bidirectional"))
    )
    (net (code "114") (name "unconnected-(U8A-PA8-Pad42)") (class "Default")
      (node (ref "U8") (pin "42") (pinfunction "PA8_42") (pintype "bidirectional"))
    )
    (net (code "115") (name "unconnected-(U8A-PA9-Pad43)") (class "Default")
      (node (ref "U8") (pin "43") (pinfunction "PA9_43") (pintype "bidirectional"))
    )
    (net (code "116") (name "unconnected-(U8A-PA10-Pad44)") (class "Default")
      (node (ref "U8") (pin "44") (pinfunction "PA10_44") (pintype "bidirectional"))
    )
    (net (code "117") (name "unconnected-(U8A-PA11-Pad45)") (class "Default")
      (node (ref "U8") (pin "45") (pinfunction "PA11_45") (pintype "bidirectional"))
    )
    (net (code "118") (name "unconnected-(U8A-PA12-Pad46)") (class "Default")
      (node (ref "U8") (pin "46") (pinfunction "PA12_46") (pintype "bidirectional"))
    )
    (net (code "119") (name "unconnected-(U8A-PA15-Pad51)") (class "Default")
      (node (ref "U8") (pin "51") (pinfunction "PA15_51") (pintype "bidirectional"))
    )
    (net (code "120") (name "unconnected-(U8B-PB0-Pad24)") (class "Default")
      (node (ref "U8") (pin "24") (pinfunction "PB0_24") (pintype "bidirectional"))
    )
    (net (code "121") (name "unconnected-(U8B-PB1-Pad25)") (class "Default")
      (node (ref "U8") (pin "25") (pinfunction "PB1_25") (pintype "bidirectional"))
    )
    (net (code "122") (name "unconnected-(U8B-PB2-Pad26)") (class "Default")
      (node (ref "U8") (pin "26") (pinfunction "PB2_26") (pintype "bidirectional"))
    )
    (net (code "123") (name "unconnected-(U8B-PB3-Pad56)") (class "Default")
      (node (ref "U8") (pin "56") (pinfunction "PB3_56") (pintype "bidirectional"))
    )
    (net (code "124") (name "unconnected-(U8B-PB4-Pad57)") (class "Default")
      (node (ref "U8") (pin "57") (pinfunction "PB4_57") (pintype "bidirectional"))
    )
    (net (code "125") (name "unconnected-(U8B-PB5-Pad58)") (class "Default")
      (node (ref "U8") (pin "58") (pinfunction "PB5_58") (pintype "bidirectional"))
    )
    (net (code "126") (name "unconnected-(U8B-PB6-Pad59)") (class "Default")
      (node (ref "U8") (pin "59") (pinfunction "PB6_59") (pintype "bidirectional"))
    )
    (net (code "127") (name "unconnected-(U8B-PB7-Pad60)") (class "Default")
      (node (ref "U8") (pin "60") (pinfunction "PB7_60") (pintype "bidirectional"))
    )
    (net (code "128") (name "unconnected-(U8B-PB9-Pad62)") (class "Default")
      (node (ref "U8") (pin "62") (pinfunction "PB9_62") (pintype "bidirectional"))
    )
    (net (code "129") (name "unconnected-(U8B-PB10-Pad30)") (class "Default")
      (node (ref "U8") (pin "30") (pinfunction "PB10_30") (pintype "bidirectional"))
    )
    (net (code "130") (name "unconnected-(U8B-PB11-Pad33)") (class "Default")
      (node (ref "U8") (pin "33") (pinfunction "PB11_33") (pintype "bidirectional"))
    )
    (net (code "131") (name "unconnected-(U8B-PB13-Pad35)") (class "Default")
      (node (ref "U8") (pin "35") (pinfunction "PB13_35") (pintype "bidirectional"))
    )
    (net (code "132") (name "unconnected-(U8B-PB14-Pad36)") (class "Default")
      (node (ref "U8") (pin "36") (pinfunction "PB14_36") (pintype "bidirectional"))
    )
    (net (code "133") (name "unconnected-(U8E-PB8-BOOT0-Pad61)") (class "Default")
      (node (ref "U8") (pin "61") (pinfunction "PB8-BOOT0_61") (pintype "bidirectional"))
    )
    (net (code "134") (name "unconnected-(U8E-PF0-OSC_IN-Pad5)") (class "Default")
      (node (ref "U8") (pin "5") (pinfunction "PF0-OSC_IN_5") (pintype "input"))
    )
    (net (code "135") (name "unconnected-(U8E-PF1-OSC_OUT-Pad6)") (class "Default")
      (node (ref "U8") (pin "6") (pinfunction "PF1-OSC_OUT_6") (pintype "output"))
    )
    (net (code "136") (name "unconnected-(U8E-VDD_2-Pad16)") (class "Default")
      (node (ref "U8") (pin "16") (pinfunction "VDD_2_16") (pintype "passive"))
    )
    (net (code "137") (name "unconnected-(U12-D-Pad4)") (class "Default")
      (node (ref "U12") (pin "4") (pinfunction "D_4") (pintype "input"))
    )
    (net (code "138") (name "unconnected-(U13-D-Pad4)") (class "Default")
      (node (ref "U13") (pin "4") (pinfunction "D_4") (pintype "input"))
    )
    (net (code "139") (name "unconnected-(U14-D-Pad4)") (class "Default")
      (node (ref "U14") (pin "4") (pinfunction "D_4") (pintype "input"))
    )
    (net (code "140") (name "unconnected-(U15-D-Pad4)") (class "Default")
      (node (ref "U15") (pin "4") (pinfunction "D_4") (pintype "input"))
    )
    (net (code "141") (name "unconnected-(U16-D-Pad4)") (class "Default")
      (node (ref "U16") (pin "4") (pinfunction "D_4") (pintype "input"))
    )
    (net (code "142") (name "unconnected-(U17-D-Pad4)") (class "Default")
      (node (ref "U17") (pin "4") (pinfunction "D_4") (pintype "input"))
    )
  )
)
